# NIXIEClock_SCH.net
KiCad netlist of a schematic drawn in Altium Designer
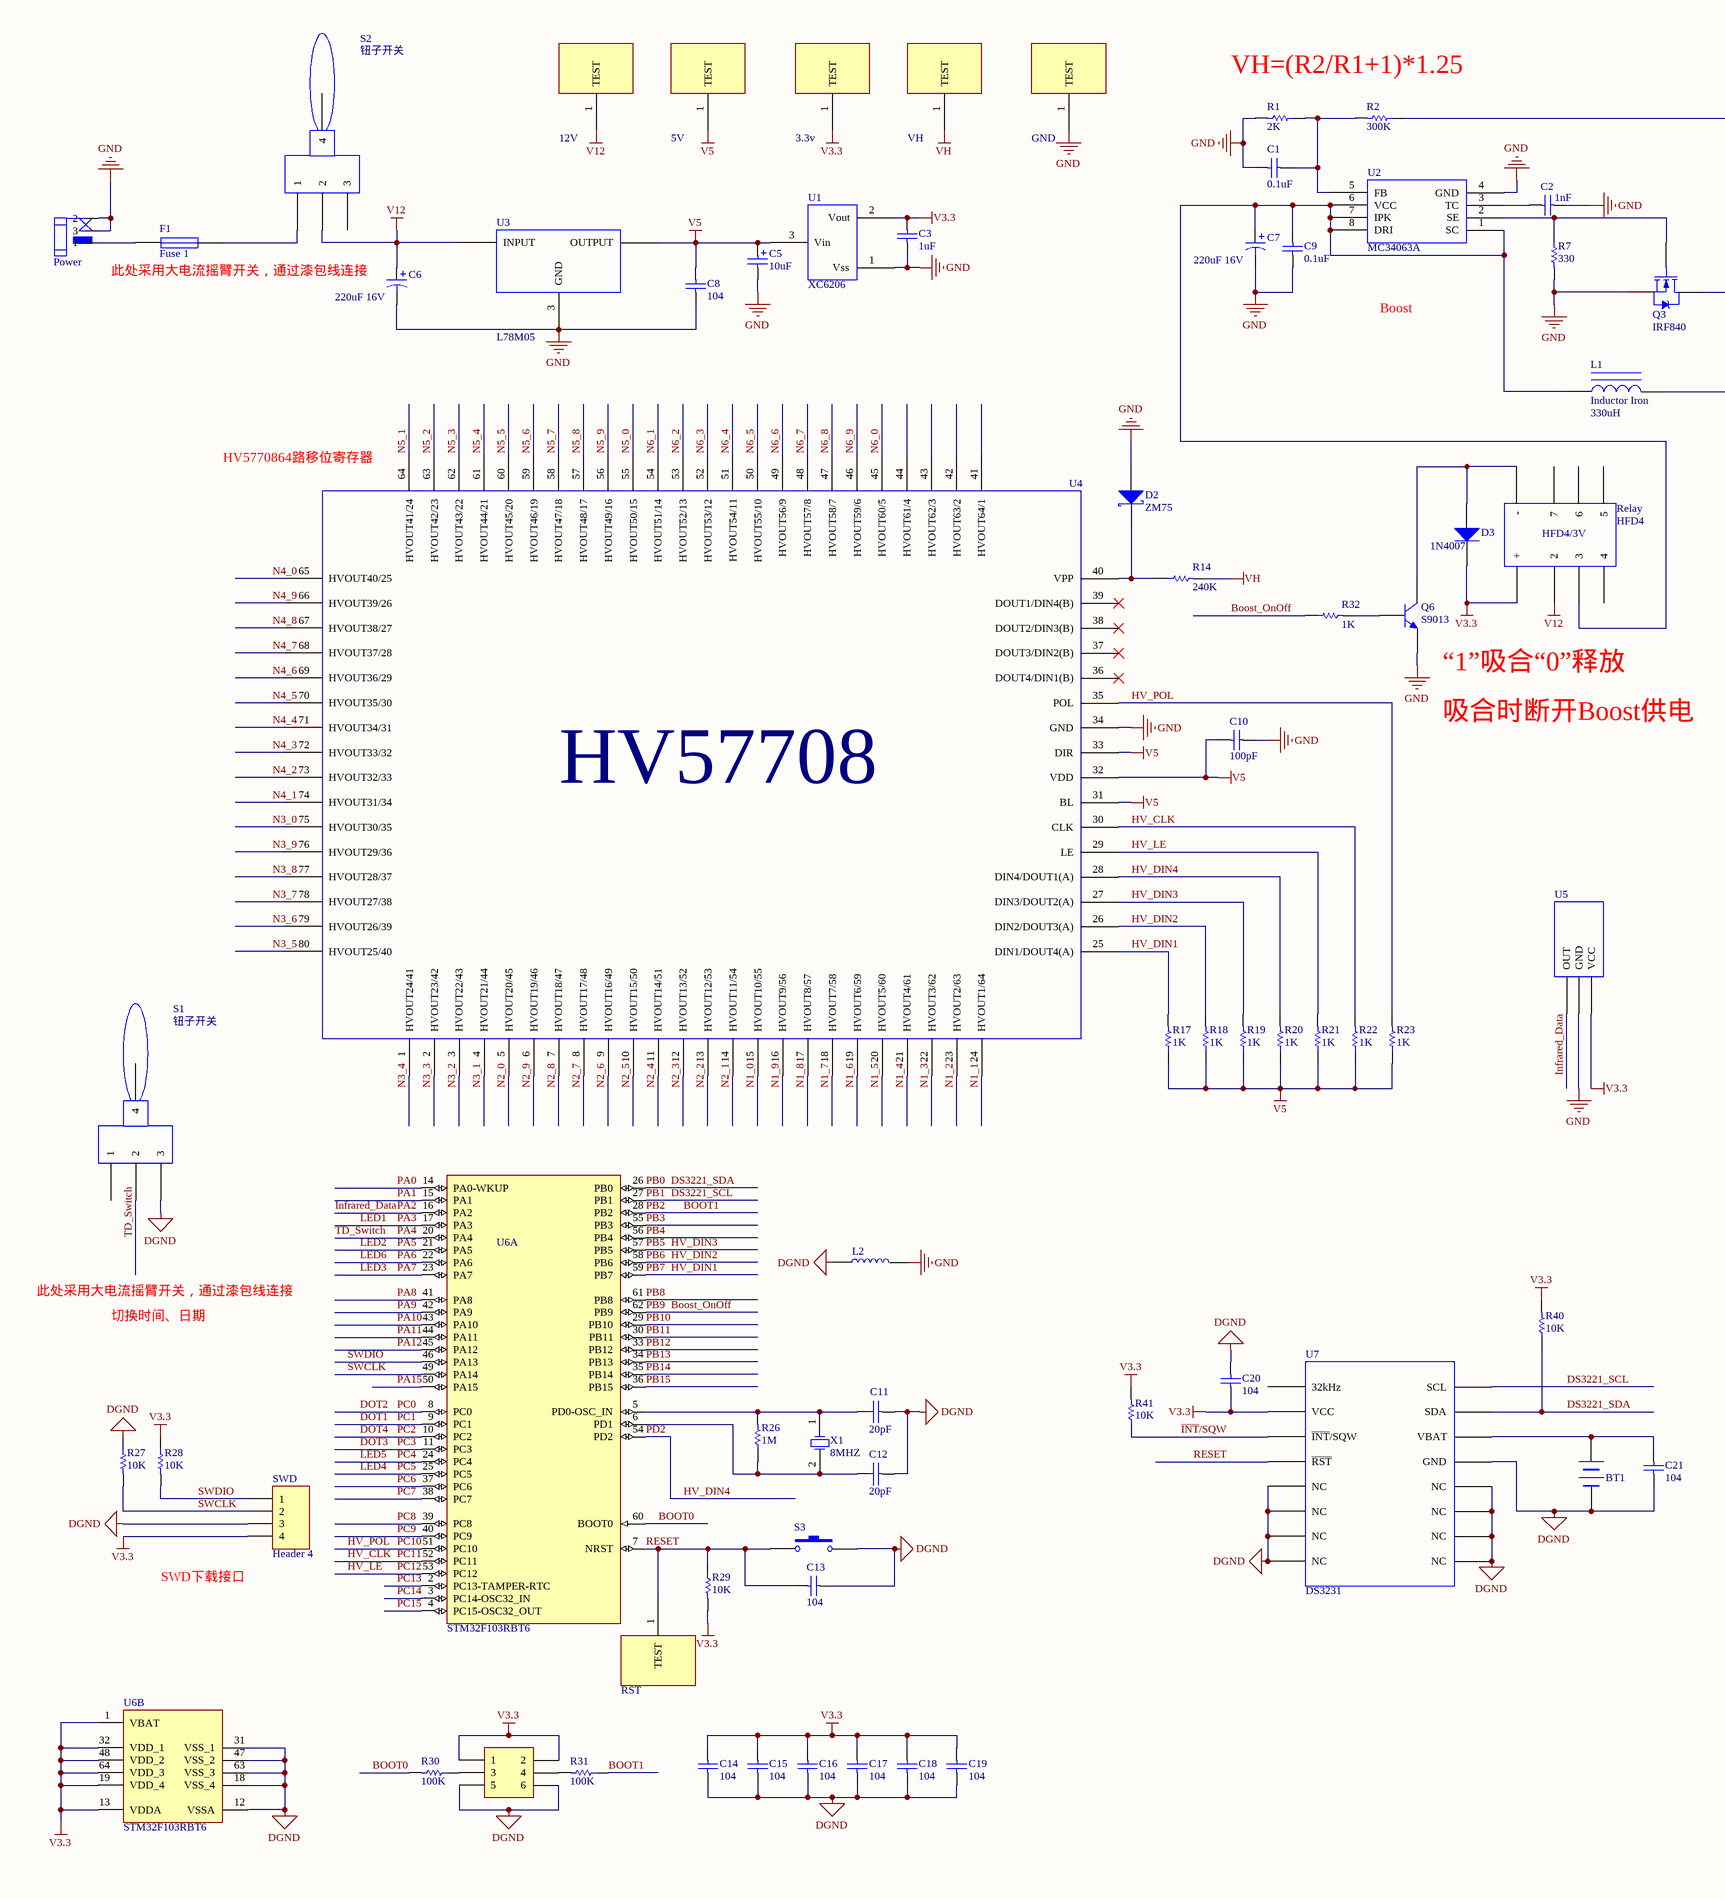
[diagram p0: NIXIEClock_SCH.SchDoc, left]
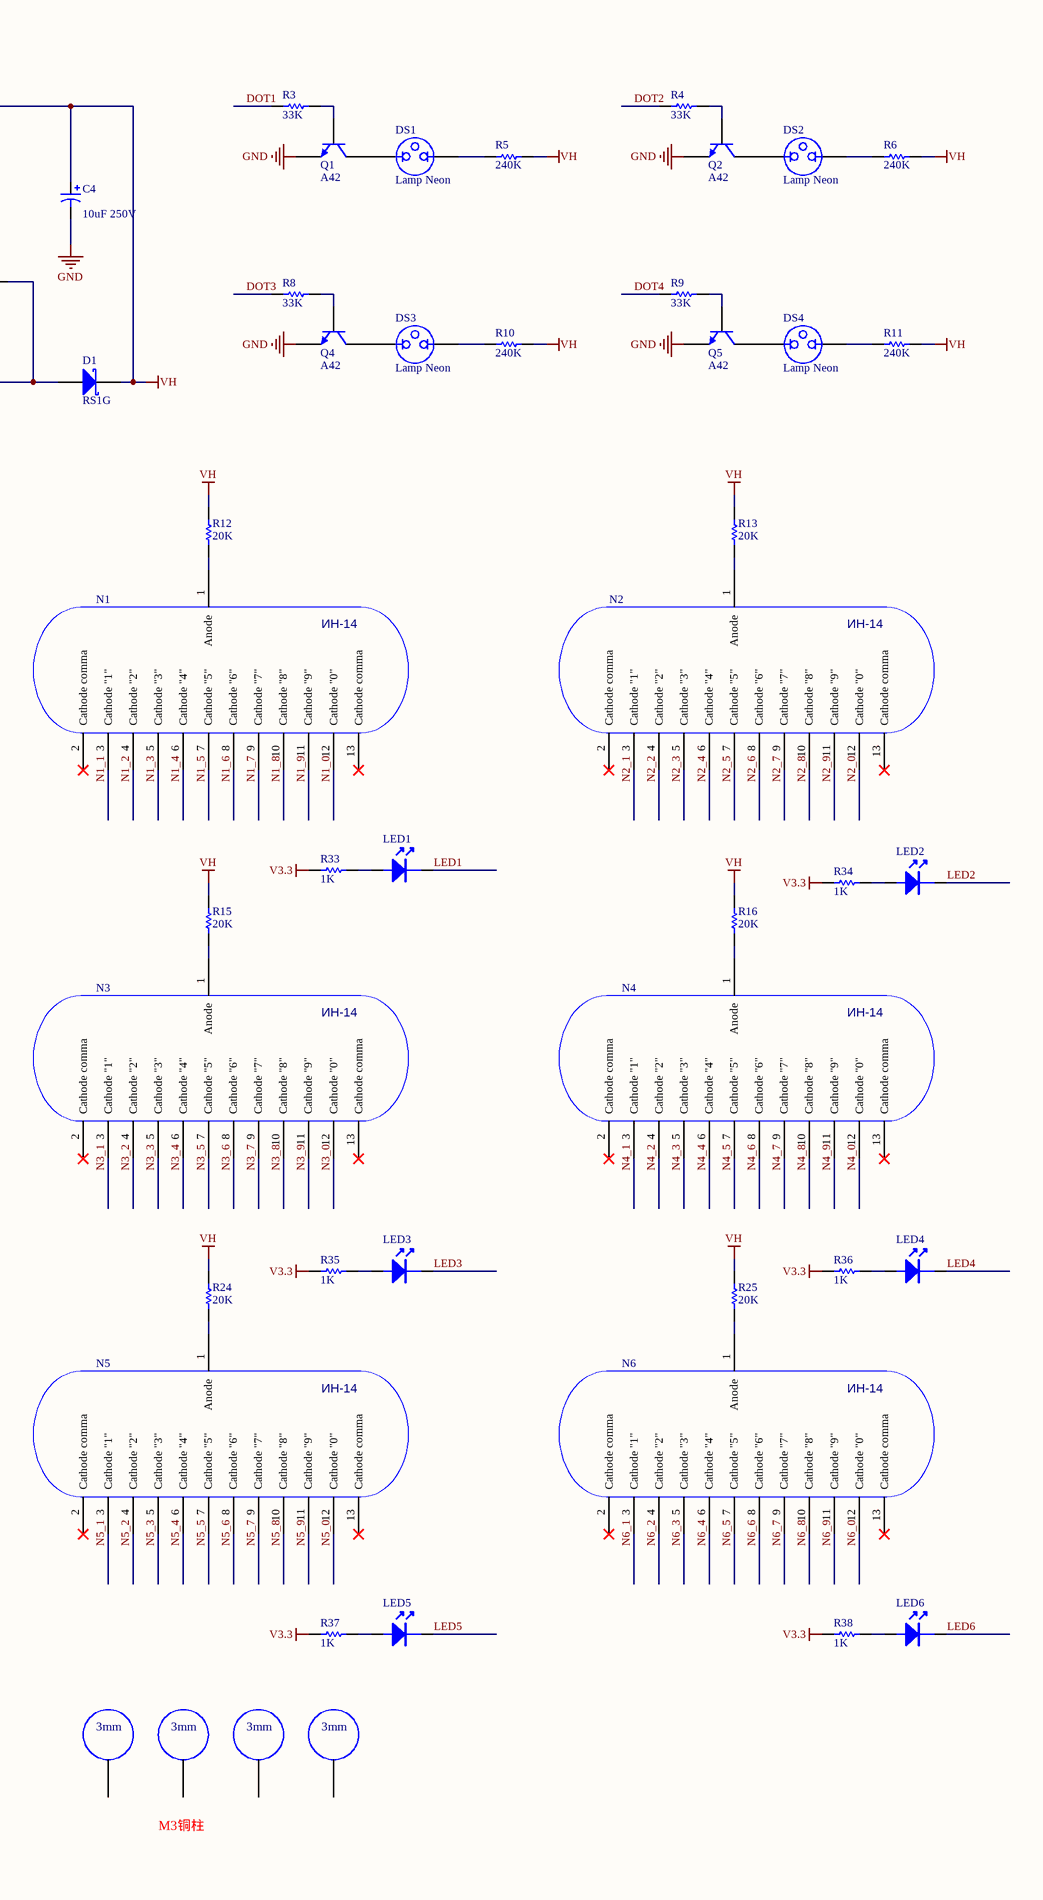
[diagram p1: NIXIEClock_SCH.SchDoc, right]

(export (version "E")
  (design (tool "Eeschema 10.0.6"))
  (components
    (comp (ref "3.3v") (value "TEST") (footprint "TEST") (libsource (lib "何龙华") (part "TEST")))
    (comp (ref "5V") (value "TEST") (footprint "TEST") (libsource (lib "何龙华") (part "TEST")))
    (comp (ref "12V") (value "TEST") (footprint "TEST") (libsource (lib "何龙华") (part "TEST")))
    (comp (ref "BOOT")
      (value "Header 3X2")
      (footprint "HDR2X3")
      (description "Header, 3-Pin, Dual row")
      (fields (field (name "PUBLISHER") "Altium Limited"))
      (libsource (lib "Miscellaneous Connectors") (part "Header 3X2"))
    )
    (comp (ref "BT1") (value "CR1220 holder") (footprint "BAT1220") (libsource (lib "何龙华") (part "BATTERY")))
    (comp (ref "C1")
      (value "0.1uF")
      (footprint "C0603")
      (description "Capacitor (Semiconductor SIM Model)")
      (fields (field (name "Comment") "Cap Semi") (field (name "PUBLISHER") "Altium Limited"))
      (libsource (lib "何龙华") (part "Cap Semi"))
    )
    (comp (ref "C2")
      (value "1nF")
      (footprint "C0603")
      (description "Capacitor (Semiconductor SIM Model)")
      (fields (field (name "Comment") "Cap Semi") (field (name "PUBLISHER") "Altium Limited"))
      (libsource (lib "何龙华") (part "Cap Semi"))
    )
    (comp (ref "C3")
      (value "1uF")
      (footprint "C0603")
      (description "Capacitor (Semiconductor SIM Model)")
      (fields (field (name "Comment") "Cap Semi") (field (name "PUBLISHER") "Altium Limited"))
      (libsource (lib "何龙华") (part "Cap Semi"))
    )
    (comp (ref "C4")
      (value "10uF 250V")
      (footprint "电容卧放2.54mm-1")
      (description "Polarized Capacitor (Radial)")
      (fields (field (name "Comment") "Cap Pol1") (field (name "PUBLISHER") "Altium Limited"))
      (libsource (lib "Miscellaneous Devices") (part "Cap Pol1"))
    )
    (comp (ref "C5")
      (value "10uF")
      (footprint "C1206")
      (description "Polarized Capacitor (Radial)")
      (fields (field (name "Comment") "Cap Pol1") (field (name "PUBLISHER") "Altium Limited"))
      (libsource (lib "何龙华") (part "Cap Pol1"))
    )
    (comp (ref "C6")
      (value "220uF 16V")
      (footprint "HONOR_63X77")
      (description "Polarized Capacitor (Radial)")
      (fields (field (name "Comment") "Cap Pol1") (field (name "PUBLISHER") "Altium Limited"))
      (libsource (lib "Miscellaneous Devices") (part "Cap Pol1"))
    )
    (comp (ref "C7")
      (value "220uF 16V")
      (footprint "HONOR_63X77")
      (description "Polarized Capacitor (Radial)")
      (fields (field (name "Comment") "Cap Pol1") (field (name "PUBLISHER") "Altium Limited"))
      (libsource (lib "Miscellaneous Devices") (part "Cap Pol1"))
    )
    (comp (ref "C8")
      (value "104")
      (footprint "C0603")
      (description "Capacitor (Semiconductor SIM Model)")
      (fields (field (name "Comment") "Cap Semi") (field (name "PUBLISHER") "Altium Limited"))
      (libsource (lib "何龙华") (part "Cap Semi"))
    )
    (comp (ref "C9")
      (value "0.1uF")
      (footprint "C0603")
      (description "Capacitor (Semiconductor SIM Model)")
      (fields (field (name "Comment") "Cap Semi") (field (name "PUBLISHER") "Altium Limited"))
      (libsource (lib "何龙华") (part "Cap Semi"))
    )
    (comp (ref "C10")
      (value "100pF")
      (footprint "C0603")
      (description "Capacitor")
      (fields (field (name "Comment") "Cap") (field (name "PUBLISHER") "Altium Limited"))
      (libsource (lib "Miscellaneous Devices") (part "Cap"))
    )
    (comp (ref "C11")
      (value "20pF")
      (footprint "C0603")
      (description "Capacitor")
      (libsource (lib "电容") (part "普通电容"))
    )
    (comp (ref "C12")
      (value "20pF")
      (footprint "C0603")
      (description "Capacitor")
      (libsource (lib "电容") (part "普通电容"))
    )
    (comp (ref "C13")
      (value "104")
      (footprint "C0603")
      (description "Capacitor (Semiconductor SIM Model)")
      (fields (field (name "Comment") "Cap Semi") (field (name "PUBLISHER") "Altium Limited"))
      (libsource (lib "何龙华") (part "Cap Semi"))
    )
    (comp (ref "C14")
      (value "104")
      (footprint "C0603")
      (description "Capacitor (Semiconductor SIM Model)")
      (fields (field (name "Comment") "Cap Semi") (field (name "PUBLISHER") "Altium Limited"))
      (libsource (lib "何龙华") (part "Cap Semi"))
    )
    (comp (ref "C15")
      (value "104")
      (footprint "C0603")
      (description "Capacitor (Semiconductor SIM Model)")
      (fields (field (name "Comment") "Cap Semi") (field (name "PUBLISHER") "Altium Limited"))
      (libsource (lib "何龙华") (part "Cap Semi"))
    )
    (comp (ref "C16")
      (value "104")
      (footprint "C0603")
      (description "Capacitor (Semiconductor SIM Model)")
      (fields (field (name "Comment") "Cap Semi") (field (name "PUBLISHER") "Altium Limited"))
      (libsource (lib "何龙华") (part "Cap Semi"))
    )
    (comp (ref "C17")
      (value "104")
      (footprint "C0603")
      (description "Capacitor (Semiconductor SIM Model)")
      (fields (field (name "Comment") "Cap Semi") (field (name "PUBLISHER") "Altium Limited"))
      (libsource (lib "何龙华") (part "Cap Semi"))
    )
    (comp (ref "C18")
      (value "104")
      (footprint "C0603")
      (description "Capacitor (Semiconductor SIM Model)")
      (fields (field (name "Comment") "Cap Semi") (field (name "PUBLISHER") "Altium Limited"))
      (libsource (lib "何龙华") (part "Cap Semi"))
    )
    (comp (ref "C19")
      (value "104")
      (footprint "C0603")
      (description "Capacitor (Semiconductor SIM Model)")
      (fields (field (name "Comment") "Cap Semi") (field (name "PUBLISHER") "Altium Limited"))
      (libsource (lib "何龙华") (part "Cap Semi"))
    )
    (comp (ref "C20")
      (value "104")
      (footprint "C0603")
      (description "Capacitor (Semiconductor SIM Model)")
      (fields (field (name "Comment") "Cap Semi") (field (name "PUBLISHER") "Altium Limited"))
      (libsource (lib "何龙华") (part "Cap Semi"))
    )
    (comp (ref "C21")
      (value "104")
      (footprint "C0603")
      (description "Capacitor (Semiconductor SIM Model)")
      (fields (field (name "Comment") "Cap Semi") (field (name "PUBLISHER") "Altium Limited"))
      (libsource (lib "何龙华") (part "Cap Semi"))
    )
    (comp (ref "D1")
      (value "RS1G")
      (footprint "SMB")
      (description "Schottky Diode")
      (fields (field (name "PUBLISHER") "Altium Limited"))
      (libsource (lib "Miscellaneous Devices") (part "D Schottky"))
    )
    (comp (ref "D2")
      (value "ZM75")
      (footprint "LL-34")
      (description "Schottky Rectifier")
      (fields (field (name "PUBLISHER") "Altium Limited"))
      (libsource (lib "Miscellaneous Devices") (part "Diode 11DQ03"))
    )
    (comp (ref "D3")
      (value "1N4007")
      (footprint "1N4007W")
      (description "1 Amp General Purpose Rectifier")
      (fields (field (name "PUBLISHER") "Altium Limited"))
      (libsource (lib "Miscellaneous Devices") (part "Diode 1N4007"))
    )
    (comp (ref "DC1") (value "Power") (footprint "DC-5mm贴片") (libsource (lib "GBY的原理图库") (part "电源插座5.4mm")))
    (comp (ref "DS1")
      (value "Lamp Neon")
      (footprint "PIN2")
      (description "Neon Lamp")
      (fields (field (name "PUBLISHER") "Altium Limited"))
      (libsource (lib "Miscellaneous Devices") (part "Lamp Neon"))
    )
    (comp (ref "DS2")
      (value "Lamp Neon")
      (footprint "PIN2")
      (description "Neon Lamp")
      (fields (field (name "PUBLISHER") "Altium Limited"))
      (libsource (lib "Miscellaneous Devices") (part "Lamp Neon"))
    )
    (comp (ref "DS3")
      (value "Lamp Neon")
      (footprint "PIN2")
      (description "Neon Lamp")
      (fields (field (name "PUBLISHER") "Altium Limited"))
      (libsource (lib "Miscellaneous Devices") (part "Lamp Neon"))
    )
    (comp (ref "DS4")
      (value "Lamp Neon")
      (footprint "PIN2")
      (description "Neon Lamp")
      (fields (field (name "PUBLISHER") "Altium Limited"))
      (libsource (lib "Miscellaneous Devices") (part "Lamp Neon"))
    )
    (comp (ref "F1")
      (value "Fuse 1")
      (footprint "SMD2018P100TF")
      (description "Fuse")
      (fields (field (name "PUBLISHER") "Altium Limited"))
      (libsource (lib "Miscellaneous Devices") (part "Fuse 1"))
    )
    (comp (ref "GND") (value "TEST") (footprint "TEST") (libsource (lib "何龙华") (part "TEST")))
    (comp (ref "L1")
      (value "Inductor Iron")
      (footprint "GDRH127")
      (description "Magnetic-Core Inductor")
      (fields (field (name "ALTIUM_VALUE") "330uH") (field (name "PUBLISHER") "Altium Limited"))
      (libsource (lib "Miscellaneous Devices") (part "Inductor Iron"))
    )
    (comp (ref "L2") (value "L0") (footprint "0805") (libsource (lib "何龙华") (part "L0")))
    (comp (ref "LED1")
      (value "LED")
      (footprint "AVX_B_3528-21")
      (description "LED发光管")
      (libsource (lib "GBY的原理图库") (part "LED"))
    )
    (comp (ref "LED2")
      (value "LED")
      (footprint "AVX_B_3528-21")
      (description "LED发光管")
      (libsource (lib "GBY的原理图库") (part "LED"))
    )
    (comp (ref "LED3")
      (value "LED")
      (footprint "AVX_B_3528-21")
      (description "LED发光管")
      (libsource (lib "GBY的原理图库") (part "LED"))
    )
    (comp (ref "LED4")
      (value "LED")
      (footprint "AVX_B_3528-21")
      (description "LED发光管")
      (libsource (lib "GBY的原理图库") (part "LED"))
    )
    (comp (ref "LED5")
      (value "LED")
      (footprint "AVX_B_3528-21")
      (description "LED发光管")
      (libsource (lib "GBY的原理图库") (part "LED"))
    )
    (comp (ref "LED6")
      (value "LED")
      (footprint "AVX_B_3528-21")
      (description "LED发光管")
      (libsource (lib "GBY的原理图库") (part "LED"))
    )
    (comp (ref "N1") (value "ИН-14") (footprint "IN14") (libsource (lib "NIXIEClock_SCHLib") (part "ИН-14")))
    (comp (ref "N2") (value "ИН-14") (footprint "IN14") (libsource (lib "NIXIEClock_SCHLib") (part "ИН-14")))
    (comp (ref "N3") (value "ИН-14") (footprint "IN14") (libsource (lib "NIXIEClock_SCHLib") (part "ИН-14")))
    (comp (ref "N4") (value "ИН-14") (footprint "IN14") (libsource (lib "NIXIEClock_SCHLib") (part "ИН-14")))
    (comp (ref "N5") (value "ИН-14") (footprint "IN14") (libsource (lib "NIXIEClock_SCHLib") (part "ИН-14")))
    (comp (ref "N6") (value "ИН-14") (footprint "IN14") (libsource (lib "NIXIEClock_SCHLib") (part "ИН-14")))
    (comp (ref "Q1")
      (value "A42")
      (footprint "SOT-23-3L")
      (description "NPN Bipolar Transistor")
      (fields (field (name "PUBLISHER") "Altium Limited"))
      (libsource (lib "何龙华") (part "NPN"))
    )
    (comp (ref "Q2")
      (value "A42")
      (footprint "SOT-23-3L")
      (description "NPN Bipolar Transistor")
      (fields (field (name "PUBLISHER") "Altium Limited"))
      (libsource (lib "何龙华") (part "NPN"))
    )
    (comp (ref "Q3")
      (value "IRF840")
      (footprint "TO-263-2L")
      (description "N-Channel Power MOSFET")
      (fields (field (name "PUBLISHER") "Altium Limited"))
      (libsource (lib "Miscellaneous Devices") (part "NMOS-2"))
    )
    (comp (ref "Q4")
      (value "A42")
      (footprint "SOT-23-3L")
      (description "NPN Bipolar Transistor")
      (fields (field (name "PUBLISHER") "Altium Limited"))
      (libsource (lib "何龙华") (part "NPN"))
    )
    (comp (ref "Q5")
      (value "A42")
      (footprint "SOT-23-3L")
      (description "NPN Bipolar Transistor")
      (fields (field (name "PUBLISHER") "Altium Limited"))
      (libsource (lib "何龙华") (part "NPN"))
    )
    (comp (ref "Q6")
      (value "S9013")
      (footprint "SOT-323")
      (description "NPN Bipolar Transistor")
      (fields (field (name "PUBLISHER") "Altium Limited"))
      (libsource (lib "何龙华") (part "NPN"))
    )
    (comp (ref "R1")
      (value "2K")
      (footprint "R0603")
      (description "Semiconductor Resistor")
      (fields (field (name "Comment") "Res Semi") (field (name "PUBLISHER") "Altium Limited"))
      (libsource (lib "何龙华") (part "Res Semi"))
    )
    (comp (ref "R2")
      (value "300K")
      (footprint "R0603")
      (description "Semiconductor Resistor")
      (fields (field (name "Comment") "Res Semi") (field (name "PUBLISHER") "Altium Limited"))
      (libsource (lib "何龙华") (part "Res Semi"))
    )
    (comp (ref "R3")
      (value "33K")
      (footprint "R0603")
      (description "Semiconductor Resistor")
      (fields (field (name "Comment") "Res Semi") (field (name "PUBLISHER") "Altium Limited"))
      (libsource (lib "何龙华") (part "Res Semi"))
    )
    (comp (ref "R4")
      (value "33K")
      (footprint "R0603")
      (description "Semiconductor Resistor")
      (fields (field (name "Comment") "Res Semi") (field (name "PUBLISHER") "Altium Limited"))
      (libsource (lib "何龙华") (part "Res Semi"))
    )
    (comp (ref "R5")
      (value "240K")
      (footprint "R0603")
      (description "Semiconductor Resistor")
      (fields (field (name "Comment") "Res Semi") (field (name "PUBLISHER") "Altium Limited"))
      (libsource (lib "何龙华") (part "Res Semi"))
    )
    (comp (ref "R6")
      (value "240K")
      (footprint "R0603")
      (description "Semiconductor Resistor")
      (fields (field (name "Comment") "Res Semi") (field (name "PUBLISHER") "Altium Limited"))
      (libsource (lib "何龙华") (part "Res Semi"))
    )
    (comp (ref "R7")
      (value "330")
      (footprint "R0603")
      (description "Semiconductor Resistor")
      (fields (field (name "Comment") "Res Semi") (field (name "PUBLISHER") "Altium Limited"))
      (libsource (lib "何龙华") (part "Res Semi"))
    )
    (comp (ref "R8")
      (value "33K")
      (footprint "R0603")
      (description "Semiconductor Resistor")
      (fields (field (name "Comment") "Res Semi") (field (name "PUBLISHER") "Altium Limited"))
      (libsource (lib "何龙华") (part "Res Semi"))
    )
    (comp (ref "R9")
      (value "33K")
      (footprint "R0603")
      (description "Semiconductor Resistor")
      (fields (field (name "Comment") "Res Semi") (field (name "PUBLISHER") "Altium Limited"))
      (libsource (lib "何龙华") (part "Res Semi"))
    )
    (comp (ref "R10")
      (value "240K")
      (footprint "R0603")
      (description "Semiconductor Resistor")
      (fields (field (name "Comment") "Res Semi") (field (name "PUBLISHER") "Altium Limited"))
      (libsource (lib "何龙华") (part "Res Semi"))
    )
    (comp (ref "R11")
      (value "240K")
      (footprint "R0603")
      (description "Semiconductor Resistor")
      (fields (field (name "Comment") "Res Semi") (field (name "PUBLISHER") "Altium Limited"))
      (libsource (lib "何龙华") (part "Res Semi"))
    )
    (comp (ref "R12")
      (value "20K")
      (footprint "R0603")
      (description "Semiconductor Resistor")
      (fields (field (name "Comment") "Res Semi") (field (name "PUBLISHER") "Altium Limited"))
      (libsource (lib "何龙华") (part "Res Semi"))
    )
    (comp (ref "R13")
      (value "20K")
      (footprint "R0603")
      (description "Semiconductor Resistor")
      (fields (field (name "Comment") "Res Semi") (field (name "PUBLISHER") "Altium Limited"))
      (libsource (lib "何龙华") (part "Res Semi"))
    )
    (comp (ref "R14")
      (value "240K")
      (footprint "R0603")
      (description "Semiconductor Resistor")
      (fields (field (name "Comment") "Res Semi") (field (name "PUBLISHER") "Altium Limited"))
      (libsource (lib "何龙华") (part "Res Semi"))
    )
    (comp (ref "R15")
      (value "20K")
      (footprint "R0603")
      (description "Semiconductor Resistor")
      (fields (field (name "Comment") "Res Semi") (field (name "PUBLISHER") "Altium Limited"))
      (libsource (lib "何龙华") (part "Res Semi"))
    )
    (comp (ref "R16")
      (value "20K")
      (footprint "R0603")
      (description "Semiconductor Resistor")
      (fields (field (name "Comment") "Res Semi") (field (name "PUBLISHER") "Altium Limited"))
      (libsource (lib "何龙华") (part "Res Semi"))
    )
    (comp (ref "R17")
      (value "1K")
      (footprint "R0603")
      (description "Semiconductor Resistor")
      (fields (field (name "Comment") "Res Semi") (field (name "PUBLISHER") "Altium Limited"))
      (libsource (lib "何龙华") (part "Res Semi"))
    )
    (comp (ref "R18")
      (value "1K")
      (footprint "R0603")
      (description "Semiconductor Resistor")
      (fields (field (name "Comment") "Res Semi") (field (name "PUBLISHER") "Altium Limited"))
      (libsource (lib "何龙华") (part "Res Semi"))
    )
    (comp (ref "R19")
      (value "1K")
      (footprint "R0603")
      (description "Semiconductor Resistor")
      (fields (field (name "Comment") "Res Semi") (field (name "PUBLISHER") "Altium Limited"))
      (libsource (lib "何龙华") (part "Res Semi"))
    )
    (comp (ref "R20")
      (value "1K")
      (footprint "R0603")
      (description "Semiconductor Resistor")
      (fields (field (name "Comment") "Res Semi") (field (name "PUBLISHER") "Altium Limited"))
      (libsource (lib "何龙华") (part "Res Semi"))
    )
    (comp (ref "R21")
      (value "1K")
      (footprint "R0603")
      (description "Semiconductor Resistor")
      (fields (field (name "Comment") "Res Semi") (field (name "PUBLISHER") "Altium Limited"))
      (libsource (lib "何龙华") (part "Res Semi"))
    )
    (comp (ref "R22")
      (value "1K")
      (footprint "R0603")
      (description "Semiconductor Resistor")
      (fields (field (name "Comment") "Res Semi") (field (name "PUBLISHER") "Altium Limited"))
      (libsource (lib "何龙华") (part "Res Semi"))
    )
    (comp (ref "R23")
      (value "1K")
      (footprint "R0603")
      (description "Semiconductor Resistor")
      (fields (field (name "Comment") "Res Semi") (field (name "PUBLISHER") "Altium Limited"))
      (libsource (lib "何龙华") (part "Res Semi"))
    )
    (comp (ref "R24")
      (value "20K")
      (footprint "R0603")
      (description "Semiconductor Resistor")
      (fields (field (name "Comment") "Res Semi") (field (name "PUBLISHER") "Altium Limited"))
      (libsource (lib "何龙华") (part "Res Semi"))
    )
    (comp (ref "R25")
      (value "20K")
      (footprint "R0603")
      (description "Semiconductor Resistor")
      (fields (field (name "Comment") "Res Semi") (field (name "PUBLISHER") "Altium Limited"))
      (libsource (lib "何龙华") (part "Res Semi"))
    )
    (comp (ref "R26")
      (value "1M")
      (footprint "R0603")
      (description "Semiconductor Resistor")
      (fields (field (name "Comment") "Res Semi") (field (name "PUBLISHER") "Altium Limited"))
      (libsource (lib "何龙华") (part "Res Semi"))
    )
    (comp (ref "R27")
      (value "10K")
      (footprint "R0603")
      (description "Semiconductor Resistor")
      (fields (field (name "Comment") "Res Semi") (field (name "PUBLISHER") "Altium Limited"))
      (libsource (lib "何龙华") (part "Res Semi"))
    )
    (comp (ref "R28")
      (value "10K")
      (footprint "R0603")
      (description "Semiconductor Resistor")
      (fields (field (name "Comment") "Res Semi") (field (name "PUBLISHER") "Altium Limited"))
      (libsource (lib "何龙华") (part "Res Semi"))
    )
    (comp (ref "R29")
      (value "10K")
      (footprint "R0603")
      (description "Semiconductor Resistor")
      (fields (field (name "Comment") "Res Semi") (field (name "PUBLISHER") "Altium Limited"))
      (libsource (lib "何龙华") (part "Res Semi"))
    )
    (comp (ref "R30")
      (value "100K")
      (footprint "R0603")
      (description "Semiconductor Resistor")
      (fields (field (name "Comment") "Res Semi") (field (name "PUBLISHER") "Altium Limited"))
      (libsource (lib "何龙华") (part "Res Semi"))
    )
    (comp (ref "R31")
      (value "100K")
      (footprint "R0603")
      (description "Semiconductor Resistor")
      (fields (field (name "Comment") "Res Semi") (field (name "PUBLISHER") "Altium Limited"))
      (libsource (lib "何龙华") (part "Res Semi"))
    )
    (comp (ref "R32")
      (value "1K")
      (footprint "R0603")
      (description "Semiconductor Resistor")
      (fields (field (name "Comment") "Res Semi") (field (name "PUBLISHER") "Altium Limited"))
      (libsource (lib "何龙华") (part "Res Semi"))
    )
    (comp (ref "R33")
      (value "1K")
      (footprint "R0603")
      (description "Semiconductor Resistor")
      (fields (field (name "Comment") "Res Semi") (field (name "PUBLISHER") "Altium Limited"))
      (libsource (lib "何龙华") (part "Res Semi"))
    )
    (comp (ref "R34")
      (value "1K")
      (footprint "R0603")
      (description "Semiconductor Resistor")
      (fields (field (name "Comment") "Res Semi") (field (name "PUBLISHER") "Altium Limited"))
      (libsource (lib "何龙华") (part "Res Semi"))
    )
    (comp (ref "R35")
      (value "1K")
      (footprint "R0603")
      (description "Semiconductor Resistor")
      (fields (field (name "Comment") "Res Semi") (field (name "PUBLISHER") "Altium Limited"))
      (libsource (lib "何龙华") (part "Res Semi"))
    )
    (comp (ref "R36")
      (value "1K")
      (footprint "R0603")
      (description "Semiconductor Resistor")
      (fields (field (name "Comment") "Res Semi") (field (name "PUBLISHER") "Altium Limited"))
      (libsource (lib "何龙华") (part "Res Semi"))
    )
    (comp (ref "R37")
      (value "1K")
      (footprint "R0603")
      (description "Semiconductor Resistor")
      (fields (field (name "Comment") "Res Semi") (field (name "PUBLISHER") "Altium Limited"))
      (libsource (lib "何龙华") (part "Res Semi"))
    )
    (comp (ref "R38")
      (value "1K")
      (footprint "R0603")
      (description "Semiconductor Resistor")
      (fields (field (name "Comment") "Res Semi") (field (name "PUBLISHER") "Altium Limited"))
      (libsource (lib "何龙华") (part "Res Semi"))
    )
    (comp (ref "R40")
      (value "10K")
      (footprint "R0603")
      (description "Semiconductor Resistor")
      (fields (field (name "Comment") "Res Semi") (field (name "PUBLISHER") "Altium Limited"))
      (libsource (lib "何龙华") (part "Res Semi"))
    )
    (comp (ref "R41")
      (value "10K")
      (footprint "R0603")
      (description "Semiconductor Resistor")
      (fields (field (name "Comment") "Res Semi") (field (name "PUBLISHER") "Altium Limited"))
      (libsource (lib "何龙华") (part "Res Semi"))
    )
    (comp (ref "Relay") (value "HFD4") (footprint "HFD4") (libsource (lib "NIXIEClock") (part "Relay")))
    (comp (ref "RST") (value "TEST") (footprint "TEST") (libsource (lib "") (part "TEST_1")))
    (comp (ref "S1") (value "钮子开关") (footprint "钮子开关6mm") (libsource (lib "NIXIEClock_SCHLib") (part "钮子开关")))
    (comp (ref "S2") (value "钮子开关") (footprint "钮子开关6mm") (libsource (lib "NIXIEClock_SCHLib") (part "钮子开关")))
    (comp (ref "S3")
      (value "SW-PB")
      (footprint "贴片按键（红头）")
      (description "Switch")
      (fields (field (name "PUBLISHER") "Altium Limited"))
      (libsource (lib "何龙华") (part "SW-PB"))
    )
    (comp (ref "SWD")
      (value "Header 4")
      (footprint "HDR1X4")
      (description "Header, 4-Pin")
      (fields (field (name "PUBLISHER") "Altium Limited"))
      (libsource (lib "Miscellaneous Connectors") (part "Header 4"))
    )
    (comp (ref "T1") (value "铜柱") (footprint "螺丝孔-3mm") (libsource (lib "NIXIEClock_SCHLib") (part "铜柱")))
    (comp (ref "T2") (value "铜柱") (footprint "螺丝孔-3mm") (libsource (lib "NIXIEClock_SCHLib") (part "铜柱")))
    (comp (ref "T3") (value "铜柱") (footprint "螺丝孔-3mm") (libsource (lib "NIXIEClock_SCHLib") (part "铜柱")))
    (comp (ref "T4") (value "铜柱") (footprint "螺丝孔-3mm") (libsource (lib "NIXIEClock_SCHLib") (part "铜柱")))
    (comp (ref "U1")
      (value "XC6206")
      (footprint "SOT-23-3L")
      (libsource (lib "NIXIEClock_SCHLib") (part "XC6206"))
    )
    (comp (ref "U2")
      (value "MC34063A")
      (footprint "SOIC8")
      (libsource (lib "NIXIEClock_SCHLib") (part "MC34063A"))
    )
    (comp (ref "U3") (value "L78M05") (footprint "TO-252-2L") (libsource (lib "NIXIEClock") (part "L78M05")))
    (comp (ref "U4")
      (value "HV57708")
      (footprint "HV57708PG")
      (libsource (lib "NIXIEClock_SCHLib") (part "HV57708"))
    )
    (comp (ref "U5")
      (value "Infrared receiver")
      (footprint "SIP3")
      (libsource (lib "NIXIEClock_SCHLib") (part "Infrared Receiver"))
    )
    (comp (ref "U6")
      (value "STM32F103RBT6")
      (footprint "LQFP64_N")
      (libsource (lib "STMicroelectronics STM32 F1") (part "STM32F103RBT6"))
    )
    (comp (ref "U7") (value "DS3231") (footprint "SOP16_75MM") (libsource (lib "NIXIEClock") (part "DS3231")))
    (comp (ref "VH") (value "TEST") (footprint "TEST") (libsource (lib "何龙华") (part "TEST")))
    (comp (ref "X1")
      (value "8MHZ")
      (footprint "SMD2_50X32")
      (description "Crystal Oscillator")
      (fields (field (name "PUBLISHER") "Altium Limited"))
      (libsource (lib "何龙华") (part "XTAL"))
    )
  )
  (nets
    (net (code "1") (name "/BOOT0") (class "Default")
      (node (ref "R30") (pin "2") (pinfunction "2_2") (pintype "passive"))
      (node (ref "U6") (pin "60") (pinfunction "BOOT0_60") (pintype "input"))
    )
    (net (code "2") (name "/BOOT1") (class "Default")
      (node (ref "R31") (pin "1") (pinfunction "1_1") (pintype "passive"))
      (node (ref "U6") (pin "28") (pinfunction "PB2_28") (pintype "bidirectional"))
    )
    (net (code "3") (name "/Boost_OnOff") (class "Default")
      (node (ref "R32") (pin "1") (pinfunction "1_1") (pintype "passive"))
      (node (ref "U6") (pin "62") (pinfunction "PB9_62") (pintype "bidirectional"))
    )
    (net (code "4") (name "/DOT1") (class "Default")
      (node (ref "R3") (pin "2") (pinfunction "2_2") (pintype "passive"))
      (node (ref "U6") (pin "9") (pinfunction "PC1_9") (pintype "bidirectional"))
    )
    (net (code "5") (name "/DOT2") (class "Default")
      (node (ref "R4") (pin "2") (pinfunction "2_2") (pintype "passive"))
      (node (ref "U6") (pin "8") (pinfunction "PC0_8") (pintype "bidirectional"))
    )
    (net (code "6") (name "/DOT3") (class "Default")
      (node (ref "R8") (pin "2") (pinfunction "2_2") (pintype "passive"))
      (node (ref "U6") (pin "11") (pinfunction "PC3_11") (pintype "bidirectional"))
    )
    (net (code "7") (name "/DOT4") (class "Default")
      (node (ref "R9") (pin "2") (pinfunction "2_2") (pintype "passive"))
      (node (ref "U6") (pin "10") (pinfunction "PC2_10") (pintype "bidirectional"))
    )
    (net (code "8") (name "/DS3221_SCL") (class "Default")
      (node (ref "U6") (pin "27") (pinfunction "PB1_27") (pintype "bidirectional"))
      (node (ref "U7") (pin "16") (pinfunction "SCL_16") (pintype "passive"))
    )
    (net (code "9") (name "/DS3221_SDA") (class "Default")
      (node (ref "R40") (pin "1") (pinfunction "1_1") (pintype "passive"))
      (node (ref "U6") (pin "26") (pinfunction "PB0_26") (pintype "bidirectional"))
      (node (ref "U7") (pin "15") (pinfunction "SDA_15") (pintype "passive"))
    )
    (net (code "10") (name "/HV_CLK") (class "Default")
      (node (ref "R22") (pin "2") (pinfunction "2_2") (pintype "passive"))
      (node (ref "U4") (pin "30") (pinfunction "CLK_30") (pintype "passive"))
      (node (ref "U6") (pin "52") (pinfunction "PC11_52") (pintype "bidirectional"))
    )
    (net (code "11") (name "/HV_DIN1") (class "Default")
      (node (ref "R17") (pin "2") (pinfunction "2_2") (pintype "passive"))
      (node (ref "U4") (pin "25") (pinfunction "DIN1/DOUT4(A)_25") (pintype "passive"))
      (node (ref "U6") (pin "59") (pinfunction "PB7_59") (pintype "bidirectional"))
    )
    (net (code "12") (name "/HV_DIN2") (class "Default")
      (node (ref "R18") (pin "2") (pinfunction "2_2") (pintype "passive"))
      (node (ref "U4") (pin "26") (pinfunction "DIN2/DOUT3(A)_26") (pintype "passive"))
      (node (ref "U6") (pin "58") (pinfunction "PB6_58") (pintype "bidirectional"))
    )
    (net (code "13") (name "/HV_DIN3") (class "Default")
      (node (ref "R19") (pin "2") (pinfunction "2_2") (pintype "passive"))
      (node (ref "U4") (pin "27") (pinfunction "DIN3/DOUT2(A)_27") (pintype "passive"))
      (node (ref "U6") (pin "57") (pinfunction "PB5_57") (pintype "bidirectional"))
    )
    (net (code "14") (name "/HV_DIN4") (class "Default")
      (node (ref "R20") (pin "2") (pinfunction "2_2") (pintype "passive"))
      (node (ref "U4") (pin "28") (pinfunction "DIN4/DOUT1(A)_28") (pintype "passive"))
      (node (ref "U6") (pin "54") (pinfunction "PD2_54") (pintype "bidirectional"))
    )
    (net (code "15") (name "/HV_LE") (class "Default")
      (node (ref "R21") (pin "2") (pinfunction "2_2") (pintype "passive"))
      (node (ref "U4") (pin "29") (pinfunction "LE_29") (pintype "passive"))
      (node (ref "U6") (pin "53") (pinfunction "PC12_53") (pintype "bidirectional"))
    )
    (net (code "16") (name "/HV_POL") (class "Default")
      (node (ref "R23") (pin "2") (pinfunction "2_2") (pintype "passive"))
      (node (ref "U4") (pin "35") (pinfunction "POL_35") (pintype "passive"))
      (node (ref "U6") (pin "51") (pinfunction "PC10_51") (pintype "bidirectional"))
    )
    (net (code "17") (name "/Infrared_Data") (class "Default")
      (node (ref "U5") (pin "1") (pinfunction "OUT_1") (pintype "passive"))
      (node (ref "U6") (pin "16") (pinfunction "PA2_16") (pintype "bidirectional"))
    )
    (net (code "18") (name "/LED1") (class "Default")
      (node (ref "LED1") (pin "2") (pinfunction "2_2") (pintype "passive"))
      (node (ref "U6") (pin "17") (pinfunction "PA3_17") (pintype "bidirectional"))
    )
    (net (code "19") (name "/LED2") (class "Default")
      (node (ref "LED2") (pin "2") (pinfunction "2_2") (pintype "passive"))
      (node (ref "U6") (pin "21") (pinfunction "PA5_21") (pintype "bidirectional"))
    )
    (net (code "20") (name "/LED3") (class "Default")
      (node (ref "LED3") (pin "2") (pinfunction "2_2") (pintype "passive"))
      (node (ref "U6") (pin "23") (pinfunction "PA7_23") (pintype "bidirectional"))
    )
    (net (code "21") (name "/LED4") (class "Default")
      (node (ref "LED4") (pin "2") (pinfunction "2_2") (pintype "passive"))
      (node (ref "U6") (pin "25") (pinfunction "PC5_25") (pintype "bidirectional"))
    )
    (net (code "22") (name "/LED5") (class "Default")
      (node (ref "LED5") (pin "2") (pinfunction "2_2") (pintype "passive"))
      (node (ref "U6") (pin "24") (pinfunction "PC4_24") (pintype "bidirectional"))
    )
    (net (code "23") (name "/LED6") (class "Default")
      (node (ref "LED6") (pin "2") (pinfunction "2_2") (pintype "passive"))
      (node (ref "U6") (pin "22") (pinfunction "PA6_22") (pintype "bidirectional"))
    )
    (net (code "24") (name "/N1_0") (class "Default")
      (node (ref "N1") (pin "12") (pinfunction "Cathode_\"0\"_12") (pintype "passive"))
      (node (ref "U4") (pin "15") (pinfunction "HVOUT10/55_15") (pintype "passive"))
    )
    (net (code "25") (name "/N1_1") (class "Default")
      (node (ref "N1") (pin "3") (pinfunction "Cathode_\"1\"_3") (pintype "passive"))
      (node (ref "U4") (pin "24") (pinfunction "HVOUT1/64_24") (pintype "passive"))
    )
    (net (code "26") (name "/N1_2") (class "Default")
      (node (ref "N1") (pin "4") (pinfunction "Cathode_\"2\"_4") (pintype "passive"))
      (node (ref "U4") (pin "23") (pinfunction "HVOUT2/63_23") (pintype "passive"))
    )
    (net (code "27") (name "/N1_3") (class "Default")
      (node (ref "N1") (pin "5") (pinfunction "Cathode_\"3\"_5") (pintype "passive"))
      (node (ref "U4") (pin "22") (pinfunction "HVOUT3/62_22") (pintype "passive"))
    )
    (net (code "28") (name "/N1_4") (class "Default")
      (node (ref "N1") (pin "6") (pinfunction "Cathode_\"4\"_6") (pintype "passive"))
      (node (ref "U4") (pin "21") (pinfunction "HVOUT4/61_21") (pintype "passive"))
    )
    (net (code "29") (name "/N1_5") (class "Default")
      (node (ref "N1") (pin "7") (pinfunction "Cathode_\"5\"_7") (pintype "passive"))
      (node (ref "U4") (pin "20") (pinfunction "HVOUT5/60_20") (pintype "passive"))
    )
    (net (code "30") (name "/N1_6") (class "Default")
      (node (ref "N1") (pin "8") (pinfunction "Cathode_\"6\"_8") (pintype "passive"))
      (node (ref "U4") (pin "19") (pinfunction "HVOUT6/59_19") (pintype "passive"))
    )
    (net (code "31") (name "/N1_7") (class "Default")
      (node (ref "N1") (pin "9") (pinfunction "Cathode_\"7\"_9") (pintype "passive"))
      (node (ref "U4") (pin "18") (pinfunction "HVOUT7/58_18") (pintype "passive"))
    )
    (net (code "32") (name "/N1_8") (class "Default")
      (node (ref "N1") (pin "10") (pinfunction "Cathode_\"8\"_10") (pintype "passive"))
      (node (ref "U4") (pin "17") (pinfunction "HVOUT8/57_17") (pintype "passive"))
    )
    (net (code "33") (name "/N1_9") (class "Default")
      (node (ref "N1") (pin "11") (pinfunction "Cathode_\"9\"_11") (pintype "passive"))
      (node (ref "U4") (pin "16") (pinfunction "HVOUT9/56_16") (pintype "passive"))
    )
    (net (code "34") (name "/N2_0") (class "Default")
      (node (ref "N2") (pin "12") (pinfunction "Cathode_\"0\"_12") (pintype "passive"))
      (node (ref "U4") (pin "5") (pinfunction "HVOUT20/45_5") (pintype "passive"))
    )
    (net (code "35") (name "/N2_1") (class "Default")
      (node (ref "N2") (pin "3") (pinfunction "Cathode_\"1\"_3") (pintype "passive"))
      (node (ref "U4") (pin "14") (pinfunction "HVOUT11/54_14") (pintype "passive"))
    )
    (net (code "36") (name "/N2_2") (class "Default")
      (node (ref "N2") (pin "4") (pinfunction "Cathode_\"2\"_4") (pintype "passive"))
      (node (ref "U4") (pin "13") (pinfunction "HVOUT12/53_13") (pintype "passive"))
    )
    (net (code "37") (name "/N2_3") (class "Default")
      (node (ref "N2") (pin "5") (pinfunction "Cathode_\"3\"_5") (pintype "passive"))
      (node (ref "U4") (pin "12") (pinfunction "HVOUT13/52_12") (pintype "passive"))
    )
    (net (code "38") (name "/N2_4") (class "Default")
      (node (ref "N2") (pin "6") (pinfunction "Cathode_\"4\"_6") (pintype "passive"))
      (node (ref "U4") (pin "11") (pinfunction "HVOUT14/51_11") (pintype "passive"))
    )
    (net (code "39") (name "/N2_5") (class "Default")
      (node (ref "N2") (pin "7") (pinfunction "Cathode_\"5\"_7") (pintype "passive"))
      (node (ref "U4") (pin "10") (pinfunction "HVOUT15/50_10") (pintype "passive"))
    )
    (net (code "40") (name "/N2_6") (class "Default")
      (node (ref "N2") (pin "8") (pinfunction "Cathode_\"6\"_8") (pintype "passive"))
      (node (ref "U4") (pin "9") (pinfunction "HVOUT16/49_9") (pintype "passive"))
    )
    (net (code "41") (name "/N2_7") (class "Default")
      (node (ref "N2") (pin "9") (pinfunction "Cathode_\"7\"_9") (pintype "passive"))
      (node (ref "U4") (pin "8") (pinfunction "HVOUT17/48_8") (pintype "passive"))
    )
    (net (code "42") (name "/N2_8") (class "Default")
      (node (ref "N2") (pin "10") (pinfunction "Cathode_\"8\"_10") (pintype "passive"))
      (node (ref "U4") (pin "7") (pinfunction "HVOUT18/47_7") (pintype "passive"))
    )
    (net (code "43") (name "/N2_9") (class "Default")
      (node (ref "N2") (pin "11") (pinfunction "Cathode_\"9\"_11") (pintype "passive"))
      (node (ref "U4") (pin "6") (pinfunction "HVOUT19/46_6") (pintype "passive"))
    )
    (net (code "44") (name "/N3_0") (class "Default")
      (node (ref "N3") (pin "12") (pinfunction "Cathode_\"0\"_12") (pintype "passive"))
      (node (ref "U4") (pin "75") (pinfunction "HVOUT30/35_75") (pintype "passive"))
    )
    (net (code "45") (name "/N3_1") (class "Default")
      (node (ref "N3") (pin "3") (pinfunction "Cathode_\"1\"_3") (pintype "passive"))
      (node (ref "U4") (pin "4") (pinfunction "HVOUT21/44_4") (pintype "passive"))
    )
    (net (code "46") (name "/N3_2") (class "Default")
      (node (ref "N3") (pin "4") (pinfunction "Cathode_\"2\"_4") (pintype "passive"))
      (node (ref "U4") (pin "3") (pinfunction "HVOUT22/43_3") (pintype "passive"))
    )
    (net (code "47") (name "/N3_3") (class "Default")
      (node (ref "N3") (pin "5") (pinfunction "Cathode_\"3\"_5") (pintype "passive"))
      (node (ref "U4") (pin "2") (pinfunction "HVOUT23/42_2") (pintype "passive"))
    )
    (net (code "48") (name "/N3_4") (class "Default")
      (node (ref "N3") (pin "6") (pinfunction "Cathode_\"4\"_6") (pintype "passive"))
      (node (ref "U4") (pin "1") (pinfunction "HVOUT24/41_1") (pintype "passive"))
    )
    (net (code "49") (name "/N3_5") (class "Default")
      (node (ref "N3") (pin "7") (pinfunction "Cathode_\"5\"_7") (pintype "passive"))
      (node (ref "U4") (pin "80") (pinfunction "HVOUT25/40_80") (pintype "passive"))
    )
    (net (code "50") (name "/N3_6") (class "Default")
      (node (ref "N3") (pin "8") (pinfunction "Cathode_\"6\"_8") (pintype "passive"))
      (node (ref "U4") (pin "79") (pinfunction "HVOUT26/39_79") (pintype "passive"))
    )
    (net (code "51") (name "/N3_7") (class "Default")
      (node (ref "N3") (pin "9") (pinfunction "Cathode_\"7\"_9") (pintype "passive"))
      (node (ref "U4") (pin "78") (pinfunction "HVOUT27/38_78") (pintype "passive"))
    )
    (net (code "52") (name "/N3_8") (class "Default")
      (node (ref "N3") (pin "10") (pinfunction "Cathode_\"8\"_10") (pintype "passive"))
      (node (ref "U4") (pin "77") (pinfunction "HVOUT28/37_77") (pintype "passive"))
    )
    (net (code "53") (name "/N3_9") (class "Default")
      (node (ref "N3") (pin "11") (pinfunction "Cathode_\"9\"_11") (pintype "passive"))
      (node (ref "U4") (pin "76") (pinfunction "HVOUT29/36_76") (pintype "passive"))
    )
    (net (code "54") (name "/N4_0") (class "Default")
      (node (ref "N4") (pin "12") (pinfunction "Cathode_\"0\"_12") (pintype "passive"))
      (node (ref "U4") (pin "65") (pinfunction "HVOUT40/25_65") (pintype "passive"))
    )
    (net (code "55") (name "/N4_1") (class "Default")
      (node (ref "N4") (pin "3") (pinfunction "Cathode_\"1\"_3") (pintype "passive"))
      (node (ref "U4") (pin "74") (pinfunction "HVOUT31/34_74") (pintype "passive"))
    )
    (net (code "56") (name "/N4_2") (class "Default")
      (node (ref "N4") (pin "4") (pinfunction "Cathode_\"2\"_4") (pintype "passive"))
      (node (ref "U4") (pin "73") (pinfunction "HVOUT32/33_73") (pintype "passive"))
    )
    (net (code "57") (name "/N4_3") (class "Default")
      (node (ref "N4") (pin "5") (pinfunction "Cathode_\"3\"_5") (pintype "passive"))
      (node (ref "U4") (pin "72") (pinfunction "HVOUT33/32_72") (pintype "passive"))
    )
    (net (code "58") (name "/N4_4") (class "Default")
      (node (ref "N4") (pin "6") (pinfunction "Cathode_\"4\"_6") (pintype "passive"))
      (node (ref "U4") (pin "71") (pinfunction "HVOUT34/31_71") (pintype "passive"))
    )
    (net (code "59") (name "/N4_5") (class "Default")
      (node (ref "N4") (pin "7") (pinfunction "Cathode_\"5\"_7") (pintype "passive"))
      (node (ref "U4") (pin "70") (pinfunction "HVOUT35/30_70") (pintype "passive"))
    )
    (net (code "60") (name "/N4_6") (class "Default")
      (node (ref "N4") (pin "8") (pinfunction "Cathode_\"6\"_8") (pintype "passive"))
      (node (ref "U4") (pin "69") (pinfunction "HVOUT36/29_69") (pintype "passive"))
    )
    (net (code "61") (name "/N4_7") (class "Default")
      (node (ref "N4") (pin "9") (pinfunction "Cathode_\"7\"_9") (pintype "passive"))
      (node (ref "U4") (pin "68") (pinfunction "HVOUT37/28_68") (pintype "passive"))
    )
    (net (code "62") (name "/N4_8") (class "Default")
      (node (ref "N4") (pin "10") (pinfunction "Cathode_\"8\"_10") (pintype "passive"))
      (node (ref "U4") (pin "67") (pinfunction "HVOUT38/27_67") (pintype "passive"))
    )
    (net (code "63") (name "/N4_9") (class "Default")
      (node (ref "N4") (pin "11") (pinfunction "Cathode_\"9\"_11") (pintype "passive"))
      (node (ref "U4") (pin "66") (pinfunction "HVOUT39/26_66") (pintype "passive"))
    )
    (net (code "64") (name "/N5_0") (class "Default")
      (node (ref "N5") (pin "12") (pinfunction "Cathode_\"0\"_12") (pintype "passive"))
      (node (ref "U4") (pin "55") (pinfunction "HVOUT50/15_55") (pintype "passive"))
    )
    (net (code "65") (name "/N5_1") (class "Default")
      (node (ref "N5") (pin "3") (pinfunction "Cathode_\"1\"_3") (pintype "passive"))
      (node (ref "U4") (pin "64") (pinfunction "HVOUT41/24_64") (pintype "passive"))
    )
    (net (code "66") (name "/N5_2") (class "Default")
      (node (ref "N5") (pin "4") (pinfunction "Cathode_\"2\"_4") (pintype "passive"))
      (node (ref "U4") (pin "63") (pinfunction "HVOUT42/23_63") (pintype "passive"))
    )
    (net (code "67") (name "/N5_3") (class "Default")
      (node (ref "N5") (pin "5") (pinfunction "Cathode_\"3\"_5") (pintype "passive"))
      (node (ref "U4") (pin "62") (pinfunction "HVOUT43/22_62") (pintype "passive"))
    )
    (net (code "68") (name "/N5_4") (class "Default")
      (node (ref "N5") (pin "6") (pinfunction "Cathode_\"4\"_6") (pintype "passive"))
      (node (ref "U4") (pin "61") (pinfunction "HVOUT44/21_61") (pintype "passive"))
    )
    (net (code "69") (name "/N5_5") (class "Default")
      (node (ref "N5") (pin "7") (pinfunction "Cathode_\"5\"_7") (pintype "passive"))
      (node (ref "U4") (pin "60") (pinfunction "HVOUT45/20_60") (pintype "passive"))
    )
    (net (code "70") (name "/N5_6") (class "Default")
      (node (ref "N5") (pin "8") (pinfunction "Cathode_\"6\"_8") (pintype "passive"))
      (node (ref "U4") (pin "59") (pinfunction "HVOUT46/19_59") (pintype "passive"))
    )
    (net (code "71") (name "/N5_7") (class "Default")
      (node (ref "N5") (pin "9") (pinfunction "Cathode_\"7\"_9") (pintype "passive"))
      (node (ref "U4") (pin "58") (pinfunction "HVOUT47/18_58") (pintype "passive"))
    )
    (net (code "72") (name "/N5_8") (class "Default")
      (node (ref "N5") (pin "10") (pinfunction "Cathode_\"8\"_10") (pintype "passive"))
      (node (ref "U4") (pin "57") (pinfunction "HVOUT48/17_57") (pintype "passive"))
    )
    (net (code "73") (name "/N5_9") (class "Default")
      (node (ref "N5") (pin "11") (pinfunction "Cathode_\"9\"_11") (pintype "passive"))
      (node (ref "U4") (pin "56") (pinfunction "HVOUT49/16_56") (pintype "passive"))
    )
    (net (code "74") (name "/N6_0") (class "Default")
      (node (ref "N6") (pin "12") (pinfunction "Cathode_\"0\"_12") (pintype "passive"))
      (node (ref "U4") (pin "45") (pinfunction "HVOUT60/5_45") (pintype "passive"))
    )
    (net (code "75") (name "/N6_1") (class "Default")
      (node (ref "N6") (pin "3") (pinfunction "Cathode_\"1\"_3") (pintype "passive"))
      (node (ref "U4") (pin "54") (pinfunction "HVOUT51/14_54") (pintype "passive"))
    )
    (net (code "76") (name "/N6_2") (class "Default")
      (node (ref "N6") (pin "4") (pinfunction "Cathode_\"2\"_4") (pintype "passive"))
      (node (ref "U4") (pin "53") (pinfunction "HVOUT52/13_53") (pintype "passive"))
    )
    (net (code "77") (name "/N6_3") (class "Default")
      (node (ref "N6") (pin "5") (pinfunction "Cathode_\"3\"_5") (pintype "passive"))
      (node (ref "U4") (pin "52") (pinfunction "HVOUT53/12_52") (pintype "passive"))
    )
    (net (code "78") (name "/N6_4") (class "Default")
      (node (ref "N6") (pin "6") (pinfunction "Cathode_\"4\"_6") (pintype "passive"))
      (node (ref "U4") (pin "51") (pinfunction "HVOUT54/11_51") (pintype "passive"))
    )
    (net (code "79") (name "/N6_5") (class "Default")
      (node (ref "N6") (pin "7") (pinfunction "Cathode_\"5\"_7") (pintype "passive"))
      (node (ref "U4") (pin "50") (pinfunction "HVOUT55/10_50") (pintype "passive"))
    )
    (net (code "80") (name "/N6_6") (class "Default")
      (node (ref "N6") (pin "8") (pinfunction "Cathode_\"6\"_8") (pintype "passive"))
      (node (ref "U4") (pin "49") (pinfunction "HVOUT56/9_49") (pintype "passive"))
    )
    (net (code "81") (name "/N6_7") (class "Default")
      (node (ref "N6") (pin "9") (pinfunction "Cathode_\"7\"_9") (pintype "passive"))
      (node (ref "U4") (pin "48") (pinfunction "HVOUT57/8_48") (pintype "passive"))
    )
    (net (code "82") (name "/N6_8") (class "Default")
      (node (ref "N6") (pin "10") (pinfunction "Cathode_\"8\"_10") (pintype "passive"))
      (node (ref "U4") (pin "47") (pinfunction "HVOUT58/7_47") (pintype "passive"))
    )
    (net (code "83") (name "/N6_9") (class "Default")
      (node (ref "N6") (pin "11") (pinfunction "Cathode_\"9\"_11") (pintype "passive"))
      (node (ref "U4") (pin "46") (pinfunction "HVOUT59/6_46") (pintype "passive"))
    )
    (net (code "84") (name "/PA0") (class "Default")
      (node (ref "U6") (pin "14") (pinfunction "PA0-WKUP_14") (pintype "bidirectional"))
    )
    (net (code "85") (name "/PA1") (class "Default")
      (node (ref "U6") (pin "15") (pinfunction "PA1_15") (pintype "bidirectional"))
    )
    (net (code "86") (name "/PA4") (class "Default")
      (node (ref "S1") (pin "2") (pinfunction "2_2") (pintype "passive"))
      (node (ref "U6") (pin "20") (pinfunction "PA4_20") (pintype "bidirectional"))
    )
    (net (code "87") (name "/PA8") (class "Default")
      (node (ref "U6") (pin "41") (pinfunction "PA8_41") (pintype "bidirectional"))
    )
    (net (code "88") (name "/PA9") (class "Default")
      (node (ref "U6") (pin "42") (pinfunction "PA9_42") (pintype "bidirectional"))
    )
    (net (code "89") (name "/PA10") (class "Default")
      (node (ref "U6") (pin "43") (pinfunction "PA10_43") (pintype "bidirectional"))
    )
    (net (code "90") (name "/PA11") (class "Default")
      (node (ref "U6") (pin "44") (pinfunction "PA11_44") (pintype "bidirectional"))
    )
    (net (code "91") (name "/PA12") (class "Default")
      (node (ref "U6") (pin "45") (pinfunction "PA12_45") (pintype "bidirectional"))
    )
    (net (code "92") (name "/PA15") (class "Default")
      (node (ref "U6") (pin "50") (pinfunction "PA15_50") (pintype "bidirectional"))
    )
    (net (code "93") (name "/PB3") (class "Default")
      (node (ref "U6") (pin "55") (pinfunction "PB3_55") (pintype "bidirectional"))
    )
    (net (code "94") (name "/PB4") (class "Default")
      (node (ref "U6") (pin "56") (pinfunction "PB4_56") (pintype "bidirectional"))
    )
    (net (code "95") (name "/PB8") (class "Default")
      (node (ref "U6") (pin "61") (pinfunction "PB8_61") (pintype "bidirectional"))
    )
    (net (code "96") (name "/PB10") (class "Default")
      (node (ref "U6") (pin "29") (pinfunction "PB10_29") (pintype "bidirectional"))
    )
    (net (code "97") (name "/PB11") (class "Default")
      (node (ref "U6") (pin "30") (pinfunction "PB11_30") (pintype "bidirectional"))
    )
    (net (code "98") (name "/PB12") (class "Default")
      (node (ref "U6") (pin "33") (pinfunction "PB12_33") (pintype "bidirectional"))
    )
    (net (code "99") (name "/PB13") (class "Default")
      (node (ref "U6") (pin "34") (pinfunction "PB13_34") (pintype "bidirectional"))
    )
    (net (code "100") (name "/PB14") (class "Default")
      (node (ref "U6") (pin "35") (pinfunction "PB14_35") (pintype "bidirectional"))
    )
    (net (code "101") (name "/PB15") (class "Default")
      (node (ref "U6") (pin "36") (pinfunction "PB15_36") (pintype "bidirectional"))
    )
    (net (code "102") (name "/PC6") (class "Default")
      (node (ref "U6") (pin "37") (pinfunction "PC6_37") (pintype "bidirectional"))
    )
    (net (code "103") (name "/PC7") (class "Default")
      (node (ref "U6") (pin "38") (pinfunction "PC7_38") (pintype "bidirectional"))
    )
    (net (code "104") (name "/PC8") (class "Default")
      (node (ref "U6") (pin "39") (pinfunction "PC8_39") (pintype "bidirectional"))
    )
    (net (code "105") (name "/PC9") (class "Default")
      (node (ref "U6") (pin "40") (pinfunction "PC9_40") (pintype "bidirectional"))
    )
    (net (code "106") (name "/PC13") (class "Default")
      (node (ref "U6") (pin "2") (pinfunction "PC13-TAMPER-RTC_2") (pintype "bidirectional"))
    )
    (net (code "107") (name "/PC14") (class "Default")
      (node (ref "U6") (pin "3") (pinfunction "PC14-OSC32_IN_3") (pintype "bidirectional"))
    )
    (net (code "108") (name "/PC15") (class "Default")
      (node (ref "U6") (pin "4") (pinfunction "PC15-OSC32_OUT_4") (pintype "bidirectional"))
    )
    (net (code "109") (name "/RESET") (class "Default")
      (node (ref "C13") (pin "1") (pinfunction "1_1") (pintype "passive"))
      (node (ref "R29") (pin "1") (pinfunction "1_1") (pintype "passive"))
      (node (ref "RST") (pin "1") (pinfunction "TEST_1") (pintype "passive"))
      (node (ref "S3") (pin "1") (pinfunction "1_1") (pintype "passive"))
      (node (ref "U6") (pin "7") (pinfunction "NRST_7") (pintype "bidirectional"))
      (node (ref "U7") (pin "4") (pinfunction "~{RST}_4") (pintype "passive"))
    )
    (net (code "110") (name "/SWCLK") (class "Default")
      (node (ref "R27") (pin "2") (pinfunction "2_2") (pintype "passive"))
      (node (ref "SWD") (pin "2") (pinfunction "2_2") (pintype "passive"))
      (node (ref "U6") (pin "49") (pinfunction "PA14_49") (pintype "bidirectional"))
    )
    (net (code "111") (name "/SWDIO") (class "Default")
      (node (ref "R28") (pin "2") (pinfunction "2_2") (pintype "passive"))
      (node (ref "SWD") (pin "1") (pinfunction "1_1") (pintype "passive"))
      (node (ref "U6") (pin "46") (pinfunction "PA13_46") (pintype "bidirectional"))
    )
    (net (code "112") (name "/~{INT}{slash}SQW") (class "Default")
      (node (ref "R41") (pin "1") (pinfunction "1_1") (pintype "passive"))
      (node (ref "U7") (pin "3") (pinfunction "~{INT}/SQW_3") (pintype "passive"))
    )
    (net (code "113") (name "DGND") (class "Default")
      (node (ref "BOOT") (pin "5") (pinfunction "5_5") (pintype "passive"))
      (node (ref "BOOT") (pin "6") (pinfunction "6_6") (pintype "passive"))
      (node (ref "BT1") (pin "2") (pinfunction "-_2") (pintype "passive"))
      (node (ref "C11") (pin "1") (pinfunction "1_1") (pintype "passive"))
      (node (ref "C12") (pin "1") (pinfunction "1_1") (pintype "passive"))
      (node (ref "C13") (pin "2") (pinfunction "2_2") (pintype "passive"))
      (node (ref "C14") (pin "1") (pinfunction "1_1") (pintype "passive"))
      (node (ref "C15") (pin "1") (pinfunction "1_1") (pintype "passive"))
      (node (ref "C16") (pin "1") (pinfunction "1_1") (pintype "passive"))
      (node (ref "C17") (pin "1") (pinfunction "1_1") (pintype "passive"))
      (node (ref "C18") (pin "1") (pinfunction "1_1") (pintype "passive"))
      (node (ref "C19") (pin "1") (pinfunction "1_1") (pintype "passive"))
      (node (ref "C20") (pin "2") (pinfunction "2_2") (pintype "passive"))
      (node (ref "C21") (pin "1") (pinfunction "1_1") (pintype "passive"))
      (node (ref "L2") (pin "1") (pinfunction "1_1") (pintype "passive"))
      (node (ref "R27") (pin "1") (pinfunction "1_1") (pintype "passive"))
      (node (ref "S1") (pin "3") (pinfunction "3_3") (pintype "passive"))
      (node (ref "S3") (pin "2") (pinfunction "2_2") (pintype "passive"))
      (node (ref "SWD") (pin "3") (pinfunction "3_3") (pintype "passive"))
      (node (ref "U6") (pin "12") (pinfunction "VSSA_12") (pintype "power_in"))
      (node (ref "U6") (pin "18") (pinfunction "VSS_4_18") (pintype "power_in"))
      (node (ref "U6") (pin "31") (pinfunction "VSS_1_31") (pintype "power_in"))
      (node (ref "U6") (pin "47") (pinfunction "VSS_2_47") (pintype "power_in"))
      (node (ref "U6") (pin "63") (pinfunction "VSS_3_63") (pintype "power_in"))
      (node (ref "U7") (pin "10") (pinfunction "NC_10") (pintype "passive"))
      (node (ref "U7") (pin "11") (pinfunction "NC_11") (pintype "passive"))
      (node (ref "U7") (pin "12") (pinfunction "NC_12") (pintype "passive"))
      (node (ref "U7") (pin "13") (pinfunction "GND_13") (pintype "passive"))
      (node (ref "U7") (pin "5") (pinfunction "NC_5") (pintype "passive"))
      (node (ref "U7") (pin "6") (pinfunction "NC_6") (pintype "passive"))
      (node (ref "U7") (pin "7") (pinfunction "NC_7") (pintype "passive"))
      (node (ref "U7") (pin "8") (pinfunction "NC_8") (pintype "passive"))
      (node (ref "U7") (pin "9") (pinfunction "NC_9") (pintype "passive"))
    )
    (net (code "114") (name "GND") (class "Default")
      (node (ref "C1") (pin "2") (pinfunction "2_2") (pintype "passive"))
      (node (ref "C10") (pin "1") (pinfunction "1_1") (pintype "passive"))
      (node (ref "C2") (pin "1") (pinfunction "1_1") (pintype "passive"))
      (node (ref "C3") (pin "1") (pinfunction "1_1") (pintype "passive"))
      (node (ref "C4") (pin "2") (pinfunction "2_2") (pintype "passive"))
      (node (ref "C5") (pin "2") (pinfunction "2_2") (pintype "passive"))
      (node (ref "C6") (pin "2") (pinfunction "2_2") (pintype "passive"))
      (node (ref "C7") (pin "2") (pinfunction "2_2") (pintype "passive"))
      (node (ref "C8") (pin "1") (pinfunction "1_1") (pintype "passive"))
      (node (ref "C9") (pin "1") (pinfunction "1_1") (pintype "passive"))
      (node (ref "D2") (pin "1") (pinfunction "A_1") (pintype "passive"))
      (node (ref "DC1") (pin "2") (pinfunction "2_2") (pintype "passive"))
      (node (ref "DC1") (pin "3") (pinfunction "3_3") (pintype "passive"))
      (node (ref "GND") (pin "1") (pinfunction "TEST_1") (pintype "passive"))
      (node (ref "L2") (pin "2") (pinfunction "2_2") (pintype "passive"))
      (node (ref "Q1") (pin "2") (pinfunction "E_2") (pintype "passive"))
      (node (ref "Q2") (pin "2") (pinfunction "E_2") (pintype "passive"))
      (node (ref "Q3") (pin "3") (pinfunction "S_3") (pintype "passive"))
      (node (ref "Q4") (pin "2") (pinfunction "E_2") (pintype "passive"))
      (node (ref "Q5") (pin "2") (pinfunction "E_2") (pintype "passive"))
      (node (ref "Q6") (pin "2") (pinfunction "E_2") (pintype "passive"))
      (node (ref "R1") (pin "2") (pinfunction "2_2") (pintype "passive"))
      (node (ref "R7") (pin "2") (pinfunction "2_2") (pintype "passive"))
      (node (ref "U1") (pin "1") (pinfunction "Vss_1") (pintype "passive"))
      (node (ref "U2") (pin "4") (pinfunction "GND_4") (pintype "passive"))
      (node (ref "U3") (pin "3") (pinfunction "GND_3") (pintype "passive"))
      (node (ref "U4") (pin "34") (pinfunction "GND_34") (pintype "passive"))
      (node (ref "U5") (pin "2") (pinfunction "GND_2") (pintype "passive"))
    )
    (net (code "115") (name "Net-(BOOT-Pad3)") (class "Default")
      (node (ref "BOOT") (pin "3") (pinfunction "3_3") (pintype "passive"))
      (node (ref "R30") (pin "1") (pinfunction "1_1") (pintype "passive"))
    )
    (net (code "116") (name "Net-(BOOT-Pad4)") (class "Default")
      (node (ref "BOOT") (pin "4") (pinfunction "4_4") (pintype "passive"))
      (node (ref "R31") (pin "2") (pinfunction "2_2") (pintype "passive"))
    )
    (net (code "117") (name "Net-(BT1-+)") (class "Default")
      (node (ref "BT1") (pin "1") (pinfunction "+_1") (pintype "passive"))
      (node (ref "C21") (pin "2") (pinfunction "2_2") (pintype "passive"))
      (node (ref "U7") (pin "14") (pinfunction "VBAT_14") (pintype "passive"))
    )
    (net (code "118") (name "Net-(D1-A)") (class "Default")
      (node (ref "D1") (pin "1") (pinfunction "A_1") (pintype "passive"))
      (node (ref "L1") (pin "2") (pinfunction "2_2") (pintype "passive"))
      (node (ref "Q3") (pin "2") (pinfunction "D_2") (pintype "passive"))
    )
    (net (code "119") (name "Net-(D2-K)") (class "Default")
      (node (ref "D2") (pin "2") (pinfunction "K_2") (pintype "passive"))
      (node (ref "R14") (pin "1") (pinfunction "1_1") (pintype "passive"))
      (node (ref "U4") (pin "40") (pinfunction "VPP_40") (pintype "passive"))
    )
    (net (code "120") (name "Net-(D3-A)") (class "Default")
      (node (ref "D3") (pin "1") (pinfunction "A_1") (pintype "passive"))
      (node (ref "Q6") (pin "3") (pinfunction "C_3") (pintype "passive"))
      (node (ref "Relay") (pin "8") (pinfunction "-_8") (pintype "passive"))
    )
    (net (code "121") (name "Net-(DC1-Pad1)") (class "Default")
      (node (ref "DC1") (pin "1") (pinfunction "1_1") (pintype "passive"))
      (node (ref "F1") (pin "1") (pinfunction "1_1") (pintype "passive"))
    )
    (net (code "122") (name "Net-(DS1-Pad2)") (class "Default")
      (node (ref "DS1") (pin "2") (pinfunction "2_2") (pintype "passive"))
      (node (ref "R5") (pin "1") (pinfunction "1_1") (pintype "passive"))
    )
    (net (code "123") (name "Net-(DS2-Pad2)") (class "Default")
      (node (ref "DS2") (pin "2") (pinfunction "2_2") (pintype "passive"))
      (node (ref "R6") (pin "1") (pinfunction "1_1") (pintype "passive"))
    )
    (net (code "124") (name "Net-(DS3-Pad2)") (class "Default")
      (node (ref "DS3") (pin "2") (pinfunction "2_2") (pintype "passive"))
      (node (ref "R10") (pin "1") (pinfunction "1_1") (pintype "passive"))
    )
    (net (code "125") (name "Net-(DS4-Pad2)") (class "Default")
      (node (ref "DS4") (pin "2") (pinfunction "2_2") (pintype "passive"))
      (node (ref "R11") (pin "1") (pinfunction "1_1") (pintype "passive"))
    )
    (net (code "126") (name "Net-(F1-Pad2)") (class "Default")
      (node (ref "F1") (pin "2") (pinfunction "2_2") (pintype "passive"))
      (node (ref "S2") (pin "1") (pinfunction "1_1") (pintype "passive"))
    )
    (net (code "127") (name "Net-(LED1-Pad1)") (class "Default")
      (node (ref "LED1") (pin "1") (pinfunction "1_1") (pintype "passive"))
      (node (ref "R33") (pin "2") (pinfunction "2_2") (pintype "passive"))
    )
    (net (code "128") (name "Net-(LED2-Pad1)") (class "Default")
      (node (ref "LED2") (pin "1") (pinfunction "1_1") (pintype "passive"))
      (node (ref "R34") (pin "2") (pinfunction "2_2") (pintype "passive"))
    )
    (net (code "129") (name "Net-(LED3-Pad1)") (class "Default")
      (node (ref "LED3") (pin "1") (pinfunction "1_1") (pintype "passive"))
      (node (ref "R35") (pin "2") (pinfunction "2_2") (pintype "passive"))
    )
    (net (code "130") (name "Net-(LED4-Pad1)") (class "Default")
      (node (ref "LED4") (pin "1") (pinfunction "1_1") (pintype "passive"))
      (node (ref "R36") (pin "2") (pinfunction "2_2") (pintype "passive"))
    )
    (net (code "131") (name "Net-(LED5-Pad1)") (class "Default")
      (node (ref "LED5") (pin "1") (pinfunction "1_1") (pintype "passive"))
      (node (ref "R37") (pin "2") (pinfunction "2_2") (pintype "passive"))
    )
    (net (code "132") (name "Net-(LED6-Pad1)") (class "Default")
      (node (ref "LED6") (pin "1") (pinfunction "1_1") (pintype "passive"))
      (node (ref "R38") (pin "2") (pinfunction "2_2") (pintype "passive"))
    )
    (net (code "133") (name "Net-(N1-Anode)") (class "Default")
      (node (ref "N1") (pin "1") (pinfunction "Anode_1") (pintype "passive"))
      (node (ref "R12") (pin "1") (pinfunction "1_1") (pintype "passive"))
    )
    (net (code "134") (name "Net-(N2-Anode)") (class "Default")
      (node (ref "N2") (pin "1") (pinfunction "Anode_1") (pintype "passive"))
      (node (ref "R13") (pin "1") (pinfunction "1_1") (pintype "passive"))
    )
    (net (code "135") (name "Net-(N3-Anode)") (class "Default")
      (node (ref "N3") (pin "1") (pinfunction "Anode_1") (pintype "passive"))
      (node (ref "R15") (pin "1") (pinfunction "1_1") (pintype "passive"))
    )
    (net (code "136") (name "Net-(N4-Anode)") (class "Default")
      (node (ref "N4") (pin "1") (pinfunction "Anode_1") (pintype "passive"))
      (node (ref "R16") (pin "1") (pinfunction "1_1") (pintype "passive"))
    )
    (net (code "137") (name "Net-(N5-Anode)") (class "Default")
      (node (ref "N5") (pin "1") (pinfunction "Anode_1") (pintype "passive"))
      (node (ref "R24") (pin "1") (pinfunction "1_1") (pintype "passive"))
    )
    (net (code "138") (name "Net-(N6-Anode)") (class "Default")
      (node (ref "N6") (pin "1") (pinfunction "Anode_1") (pintype "passive"))
      (node (ref "R25") (pin "1") (pinfunction "1_1") (pintype "passive"))
    )
    (net (code "139") (name "Net-(Q1-B)") (class "Default")
      (node (ref "Q1") (pin "1") (pinfunction "B_1") (pintype "passive"))
      (node (ref "R3") (pin "1") (pinfunction "1_1") (pintype "passive"))
    )
    (net (code "140") (name "Net-(Q1-C)") (class "Default")
      (node (ref "DS1") (pin "1") (pinfunction "1_1") (pintype "passive"))
      (node (ref "Q1") (pin "3") (pinfunction "C_3") (pintype "passive"))
    )
    (net (code "141") (name "Net-(Q2-B)") (class "Default")
      (node (ref "Q2") (pin "1") (pinfunction "B_1") (pintype "passive"))
      (node (ref "R4") (pin "1") (pinfunction "1_1") (pintype "passive"))
    )
    (net (code "142") (name "Net-(Q2-C)") (class "Default")
      (node (ref "DS2") (pin "1") (pinfunction "1_1") (pintype "passive"))
      (node (ref "Q2") (pin "3") (pinfunction "C_3") (pintype "passive"))
    )
    (net (code "143") (name "Net-(Q3-G)") (class "Default")
      (node (ref "Q3") (pin "1") (pinfunction "G_1") (pintype "passive"))
      (node (ref "R7") (pin "1") (pinfunction "1_1") (pintype "passive"))
      (node (ref "U2") (pin "2") (pinfunction "SE_2") (pintype "passive"))
    )
    (net (code "144") (name "Net-(Q4-B)") (class "Default")
      (node (ref "Q4") (pin "1") (pinfunction "B_1") (pintype "passive"))
      (node (ref "R8") (pin "1") (pinfunction "1_1") (pintype "passive"))
    )
    (net (code "145") (name "Net-(Q4-C)") (class "Default")
      (node (ref "DS3") (pin "1") (pinfunction "1_1") (pintype "passive"))
      (node (ref "Q4") (pin "3") (pinfunction "C_3") (pintype "passive"))
    )
    (net (code "146") (name "Net-(Q5-B)") (class "Default")
      (node (ref "Q5") (pin "1") (pinfunction "B_1") (pintype "passive"))
      (node (ref "R9") (pin "1") (pinfunction "1_1") (pintype "passive"))
    )
    (net (code "147") (name "Net-(Q5-C)") (class "Default")
      (node (ref "DS4") (pin "1") (pinfunction "1_1") (pintype "passive"))
      (node (ref "Q5") (pin "3") (pinfunction "C_3") (pintype "passive"))
    )
    (net (code "148") (name "Net-(Q6-B)") (class "Default")
      (node (ref "Q6") (pin "1") (pinfunction "B_1") (pintype "passive"))
      (node (ref "R32") (pin "2") (pinfunction "2_2") (pintype "passive"))
    )
    (net (code "149") (name "Net-(U2-DRI)") (class "Default")
      (node (ref "C7") (pin "1") (pinfunction "1_1") (pintype "passive"))
      (node (ref "C9") (pin "2") (pinfunction "2_2") (pintype "passive"))
      (node (ref "L1") (pin "1") (pinfunction "1_1") (pintype "passive"))
      (node (ref "Relay") (pin "3") (pinfunction "3_3") (pintype "passive"))
      (node (ref "U2") (pin "1") (pinfunction "SC_1") (pintype "passive"))
      (node (ref "U2") (pin "6") (pinfunction "VCC_6") (pintype "passive"))
      (node (ref "U2") (pin "7") (pinfunction "IPK_7") (pintype "passive"))
      (node (ref "U2") (pin "8") (pinfunction "DRI_8") (pintype "passive"))
    )
    (net (code "150") (name "Net-(U2-FB)") (class "Default")
      (node (ref "C1") (pin "1") (pinfunction "1_1") (pintype "passive"))
      (node (ref "R1") (pin "1") (pinfunction "1_1") (pintype "passive"))
      (node (ref "R2") (pin "2") (pinfunction "2_2") (pintype "passive"))
      (node (ref "U2") (pin "5") (pinfunction "FB_5") (pintype "passive"))
    )
    (net (code "151") (name "Net-(U2-TC)") (class "Default")
      (node (ref "C2") (pin "2") (pinfunction "2_2") (pintype "passive"))
      (node (ref "U2") (pin "3") (pinfunction "TC_3") (pintype "passive"))
    )
    (net (code "152") (name "Net-(U6A-PD0-OSC_IN)") (class "Default")
      (node (ref "C11") (pin "2") (pinfunction "2_2") (pintype "passive"))
      (node (ref "R26") (pin "2") (pinfunction "2_2") (pintype "passive"))
      (node (ref "U6") (pin "5") (pinfunction "PD0-OSC_IN_5") (pintype "bidirectional"))
      (node (ref "X1") (pin "1") (pinfunction "OSC1_1") (pintype "passive"))
    )
    (net (code "153") (name "Net-(U6A-PD1)") (class "Default")
      (node (ref "C12") (pin "2") (pinfunction "2_2") (pintype "passive"))
      (node (ref "R26") (pin "1") (pinfunction "1_1") (pintype "passive"))
      (node (ref "U6") (pin "6") (pinfunction "PD1_6") (pintype "bidirectional"))
      (node (ref "X1") (pin "2") (pinfunction "OSC2_2") (pintype "passive"))
    )
    (net (code "154") (name "V3.3") (class "Default")
      (node (ref "3.3v") (pin "1") (pinfunction "TEST_1") (pintype "passive"))
      (node (ref "BOOT") (pin "1") (pinfunction "1_1") (pintype "passive"))
      (node (ref "BOOT") (pin "2") (pinfunction "2_2") (pintype "passive"))
      (node (ref "C14") (pin "2") (pinfunction "2_2") (pintype "passive"))
      (node (ref "C15") (pin "2") (pinfunction "2_2") (pintype "passive"))
      (node (ref "C16") (pin "2") (pinfunction "2_2") (pintype "passive"))
      (node (ref "C17") (pin "2") (pinfunction "2_2") (pintype "passive"))
      (node (ref "C18") (pin "2") (pinfunction "2_2") (pintype "passive"))
      (node (ref "C19") (pin "2") (pinfunction "2_2") (pintype "passive"))
      (node (ref "C20") (pin "1") (pinfunction "1_1") (pintype "passive"))
      (node (ref "C3") (pin "2") (pinfunction "2_2") (pintype "passive"))
      (node (ref "D3") (pin "2") (pinfunction "K_2") (pintype "passive"))
      (node (ref "R28") (pin "1") (pinfunction "1_1") (pintype "passive"))
      (node (ref "R29") (pin "2") (pinfunction "2_2") (pintype "passive"))
      (node (ref "R33") (pin "1") (pinfunction "1_1") (pintype "passive"))
      (node (ref "R34") (pin "1") (pinfunction "1_1") (pintype "passive"))
      (node (ref "R35") (pin "1") (pinfunction "1_1") (pintype "passive"))
      (node (ref "R36") (pin "1") (pinfunction "1_1") (pintype "passive"))
      (node (ref "R37") (pin "1") (pinfunction "1_1") (pintype "passive"))
      (node (ref "R38") (pin "1") (pinfunction "1_1") (pintype "passive"))
      (node (ref "R40") (pin "2") (pinfunction "2_2") (pintype "passive"))
      (node (ref "R41") (pin "2") (pinfunction "2_2") (pintype "passive"))
      (node (ref "Relay") (pin "1") (pinfunction "+_1") (pintype "passive"))
      (node (ref "SWD") (pin "4") (pinfunction "4_4") (pintype "passive"))
      (node (ref "U1") (pin "2") (pinfunction "Vout_2") (pintype "passive"))
      (node (ref "U5") (pin "3") (pinfunction "VCC_3") (pintype "passive"))
      (node (ref "U6") (pin "1") (pinfunction "VBAT_1") (pintype "power_in"))
      (node (ref "U6") (pin "13") (pinfunction "VDDA_13") (pintype "power_in"))
      (node (ref "U6") (pin "19") (pinfunction "VDD_4_19") (pintype "power_in"))
      (node (ref "U6") (pin "32") (pinfunction "VDD_1_32") (pintype "power_in"))
      (node (ref "U6") (pin "48") (pinfunction "VDD_2_48") (pintype "power_in"))
      (node (ref "U6") (pin "64") (pinfunction "VDD_3_64") (pintype "power_in"))
      (node (ref "U7") (pin "2") (pinfunction "VCC_2") (pintype "passive"))
    )
    (net (code "155") (name "V5") (class "Default")
      (node (ref "5V") (pin "1") (pinfunction "TEST_1") (pintype "passive"))
      (node (ref "C10") (pin "2") (pinfunction "2_2") (pintype "passive"))
      (node (ref "C5") (pin "1") (pinfunction "1_1") (pintype "passive"))
      (node (ref "C8") (pin "2") (pinfunction "2_2") (pintype "passive"))
      (node (ref "R17") (pin "1") (pinfunction "1_1") (pintype "passive"))
      (node (ref "R18") (pin "1") (pinfunction "1_1") (pintype "passive"))
      (node (ref "R19") (pin "1") (pinfunction "1_1") (pintype "passive"))
      (node (ref "R20") (pin "1") (pinfunction "1_1") (pintype "passive"))
      (node (ref "R21") (pin "1") (pinfunction "1_1") (pintype "passive"))
      (node (ref "R22") (pin "1") (pinfunction "1_1") (pintype "passive"))
      (node (ref "R23") (pin "1") (pinfunction "1_1") (pintype "passive"))
      (node (ref "U1") (pin "3") (pinfunction "Vin_3") (pintype "passive"))
      (node (ref "U3") (pin "2") (pinfunction "OUTPUT_2") (pintype "passive"))
      (node (ref "U4") (pin "31") (pinfunction "BL_31") (pintype "passive"))
      (node (ref "U4") (pin "32") (pinfunction "VDD_32") (pintype "passive"))
      (node (ref "U4") (pin "33") (pinfunction "DIR_33") (pintype "passive"))
    )
    (net (code "156") (name "V12") (class "Default")
      (node (ref "12V") (pin "1") (pinfunction "TEST_1") (pintype "passive"))
      (node (ref "C6") (pin "1") (pinfunction "1_1") (pintype "passive"))
      (node (ref "Relay") (pin "2") (pinfunction "2_2") (pintype "passive"))
      (node (ref "S2") (pin "2") (pinfunction "2_2") (pintype "passive"))
      (node (ref "U3") (pin "1") (pinfunction "INPUT_1") (pintype "passive"))
    )
    (net (code "157") (name "VH") (class "Default")
      (node (ref "C4") (pin "1") (pinfunction "1_1") (pintype "passive"))
      (node (ref "D1") (pin "2") (pinfunction "K_2") (pintype "passive"))
      (node (ref "R10") (pin "2") (pinfunction "2_2") (pintype "passive"))
      (node (ref "R11") (pin "2") (pinfunction "2_2") (pintype "passive"))
      (node (ref "R12") (pin "2") (pinfunction "2_2") (pintype "passive"))
      (node (ref "R13") (pin "2") (pinfunction "2_2") (pintype "passive"))
      (node (ref "R14") (pin "2") (pinfunction "2_2") (pintype "passive"))
      (node (ref "R15") (pin "2") (pinfunction "2_2") (pintype "passive"))
      (node (ref "R16") (pin "2") (pinfunction "2_2") (pintype "passive"))
      (node (ref "R2") (pin "1") (pinfunction "1_1") (pintype "passive"))
      (node (ref "R24") (pin "2") (pinfunction "2_2") (pintype "passive"))
      (node (ref "R25") (pin "2") (pinfunction "2_2") (pintype "passive"))
      (node (ref "R5") (pin "2") (pinfunction "2_2") (pintype "passive"))
      (node (ref "R6") (pin "2") (pinfunction "2_2") (pintype "passive"))
      (node (ref "VH") (pin "1") (pinfunction "TEST_1") (pintype "passive"))
    )
    (net (code "158") (name "unconnected-(N1-Cathode_comma-Pad2)") (class "Default")
      (node (ref "N1") (pin "2") (pinfunction "Cathode_comma_2") (pintype "passive+no_connect"))
    )
    (net (code "159") (name "unconnected-(N1-Cathode_comma-Pad13)") (class "Default")
      (node (ref "N1") (pin "13") (pinfunction "Cathode_comma_13") (pintype "passive+no_connect"))
    )
    (net (code "160") (name "unconnected-(N2-Cathode_comma-Pad2)") (class "Default")
      (node (ref "N2") (pin "2") (pinfunction "Cathode_comma_2") (pintype "passive+no_connect"))
    )
    (net (code "161") (name "unconnected-(N2-Cathode_comma-Pad13)") (class "Default")
      (node (ref "N2") (pin "13") (pinfunction "Cathode_comma_13") (pintype "passive+no_connect"))
    )
    (net (code "162") (name "unconnected-(N3-Cathode_comma-Pad2)") (class "Default")
      (node (ref "N3") (pin "2") (pinfunction "Cathode_comma_2") (pintype "passive+no_connect"))
    )
    (net (code "163") (name "unconnected-(N3-Cathode_comma-Pad13)") (class "Default")
      (node (ref "N3") (pin "13") (pinfunction "Cathode_comma_13") (pintype "passive+no_connect"))
    )
    (net (code "164") (name "unconnected-(N4-Cathode_comma-Pad2)") (class "Default")
      (node (ref "N4") (pin "2") (pinfunction "Cathode_comma_2") (pintype "passive+no_connect"))
    )
    (net (code "165") (name "unconnected-(N4-Cathode_comma-Pad13)") (class "Default")
      (node (ref "N4") (pin "13") (pinfunction "Cathode_comma_13") (pintype "passive+no_connect"))
    )
    (net (code "166") (name "unconnected-(N5-Cathode_comma-Pad2)") (class "Default")
      (node (ref "N5") (pin "2") (pinfunction "Cathode_comma_2") (pintype "passive+no_connect"))
    )
    (net (code "167") (name "unconnected-(N5-Cathode_comma-Pad13)") (class "Default")
      (node (ref "N5") (pin "13") (pinfunction "Cathode_comma_13") (pintype "passive+no_connect"))
    )
    (net (code "168") (name "unconnected-(N6-Cathode_comma-Pad2)") (class "Default")
      (node (ref "N6") (pin "2") (pinfunction "Cathode_comma_2") (pintype "passive+no_connect"))
    )
    (net (code "169") (name "unconnected-(N6-Cathode_comma-Pad13)") (class "Default")
      (node (ref "N6") (pin "13") (pinfunction "Cathode_comma_13") (pintype "passive+no_connect"))
    )
    (net (code "170") (name "unconnected-(Relay-Pad4)") (class "Default")
      (node (ref "Relay") (pin "4") (pinfunction "4_4") (pintype "passive"))
    )
    (net (code "171") (name "unconnected-(Relay-Pad5)") (class "Default")
      (node (ref "Relay") (pin "5") (pinfunction "5_5") (pintype "passive"))
    )
    (net (code "172") (name "unconnected-(Relay-Pad6)") (class "Default")
      (node (ref "Relay") (pin "6") (pinfunction "6_6") (pintype "passive"))
    )
    (net (code "173") (name "unconnected-(Relay-Pad7)") (class "Default")
      (node (ref "Relay") (pin "7") (pinfunction "7_7") (pintype "passive"))
    )
    (net (code "174") (name "unconnected-(S1-Pad1)") (class "Default")
      (node (ref "S1") (pin "1") (pinfunction "1_1") (pintype "passive"))
    )
    (net (code "175") (name "unconnected-(S1-Pad4)") (class "Default")
      (node (ref "S1") (pin "4") (pinfunction "4_4") (pintype "passive"))
    )
    (net (code "176") (name "unconnected-(S2-Pad3)") (class "Default")
      (node (ref "S2") (pin "3") (pinfunction "3_3") (pintype "passive"))
    )
    (net (code "177") (name "unconnected-(S2-Pad4)") (class "Default")
      (node (ref "S2") (pin "4") (pinfunction "4_4") (pintype "passive"))
    )
    (net (code "178") (name "unconnected-(T1-Pad1)") (class "Default")
      (node (ref "T1") (pin "1") (pinfunction "1_1") (pintype "passive"))
    )
    (net (code "179") (name "unconnected-(T2-Pad1)") (class "Default")
      (node (ref "T2") (pin "1") (pinfunction "1_1") (pintype "passive"))
    )
    (net (code "180") (name "unconnected-(T3-Pad1)") (class "Default")
      (node (ref "T3") (pin "1") (pinfunction "1_1") (pintype "passive"))
    )
    (net (code "181") (name "unconnected-(T4-Pad1)") (class "Default")
      (node (ref "T4") (pin "1") (pinfunction "1_1") (pintype "passive"))
    )
    (net (code "182") (name "unconnected-(U4-DOUT1{slash}DIN4(B)-Pad39)") (class "Default")
      (node (ref "U4") (pin "39") (pinfunction "DOUT1/DIN4(B)_39") (pintype "passive+no_connect"))
    )
    (net (code "183") (name "unconnected-(U4-DOUT2{slash}DIN3(B)-Pad38)") (class "Default")
      (node (ref "U4") (pin "38") (pinfunction "DOUT2/DIN3(B)_38") (pintype "passive+no_connect"))
    )
    (net (code "184") (name "unconnected-(U4-DOUT3{slash}DIN2(B)-Pad37)") (class "Default")
      (node (ref "U4") (pin "37") (pinfunction "DOUT3/DIN2(B)_37") (pintype "passive+no_connect"))
    )
    (net (code "185") (name "unconnected-(U4-DOUT4{slash}DIN1(B)-Pad36)") (class "Default")
      (node (ref "U4") (pin "36") (pinfunction "DOUT4/DIN1(B)_36") (pintype "passive+no_connect"))
    )
    (net (code "186") (name "unconnected-(U4-HVOUT61{slash}4-Pad44)") (class "Default")
      (node (ref "U4") (pin "44") (pinfunction "HVOUT61/4_44") (pintype "passive"))
    )
    (net (code "187") (name "unconnected-(U4-HVOUT62{slash}3-Pad43)") (class "Default")
      (node (ref "U4") (pin "43") (pinfunction "HVOUT62/3_43") (pintype "passive"))
    )
    (net (code "188") (name "unconnected-(U4-HVOUT63{slash}2-Pad42)") (class "Default")
      (node (ref "U4") (pin "42") (pinfunction "HVOUT63/2_42") (pintype "passive"))
    )
    (net (code "189") (name "unconnected-(U4-HVOUT64{slash}1-Pad41)") (class "Default")
      (node (ref "U4") (pin "41") (pinfunction "HVOUT64/1_41") (pintype "passive"))
    )
    (net (code "190") (name "unconnected-(U7-32kHz-Pad1)") (class "Default")
      (node (ref "U7") (pin "1") (pinfunction "32kHz_1") (pintype "passive"))
    )
  )
)
